# LineBot_2016.net
KiCad netlist of a schematic drawn in EAGLE
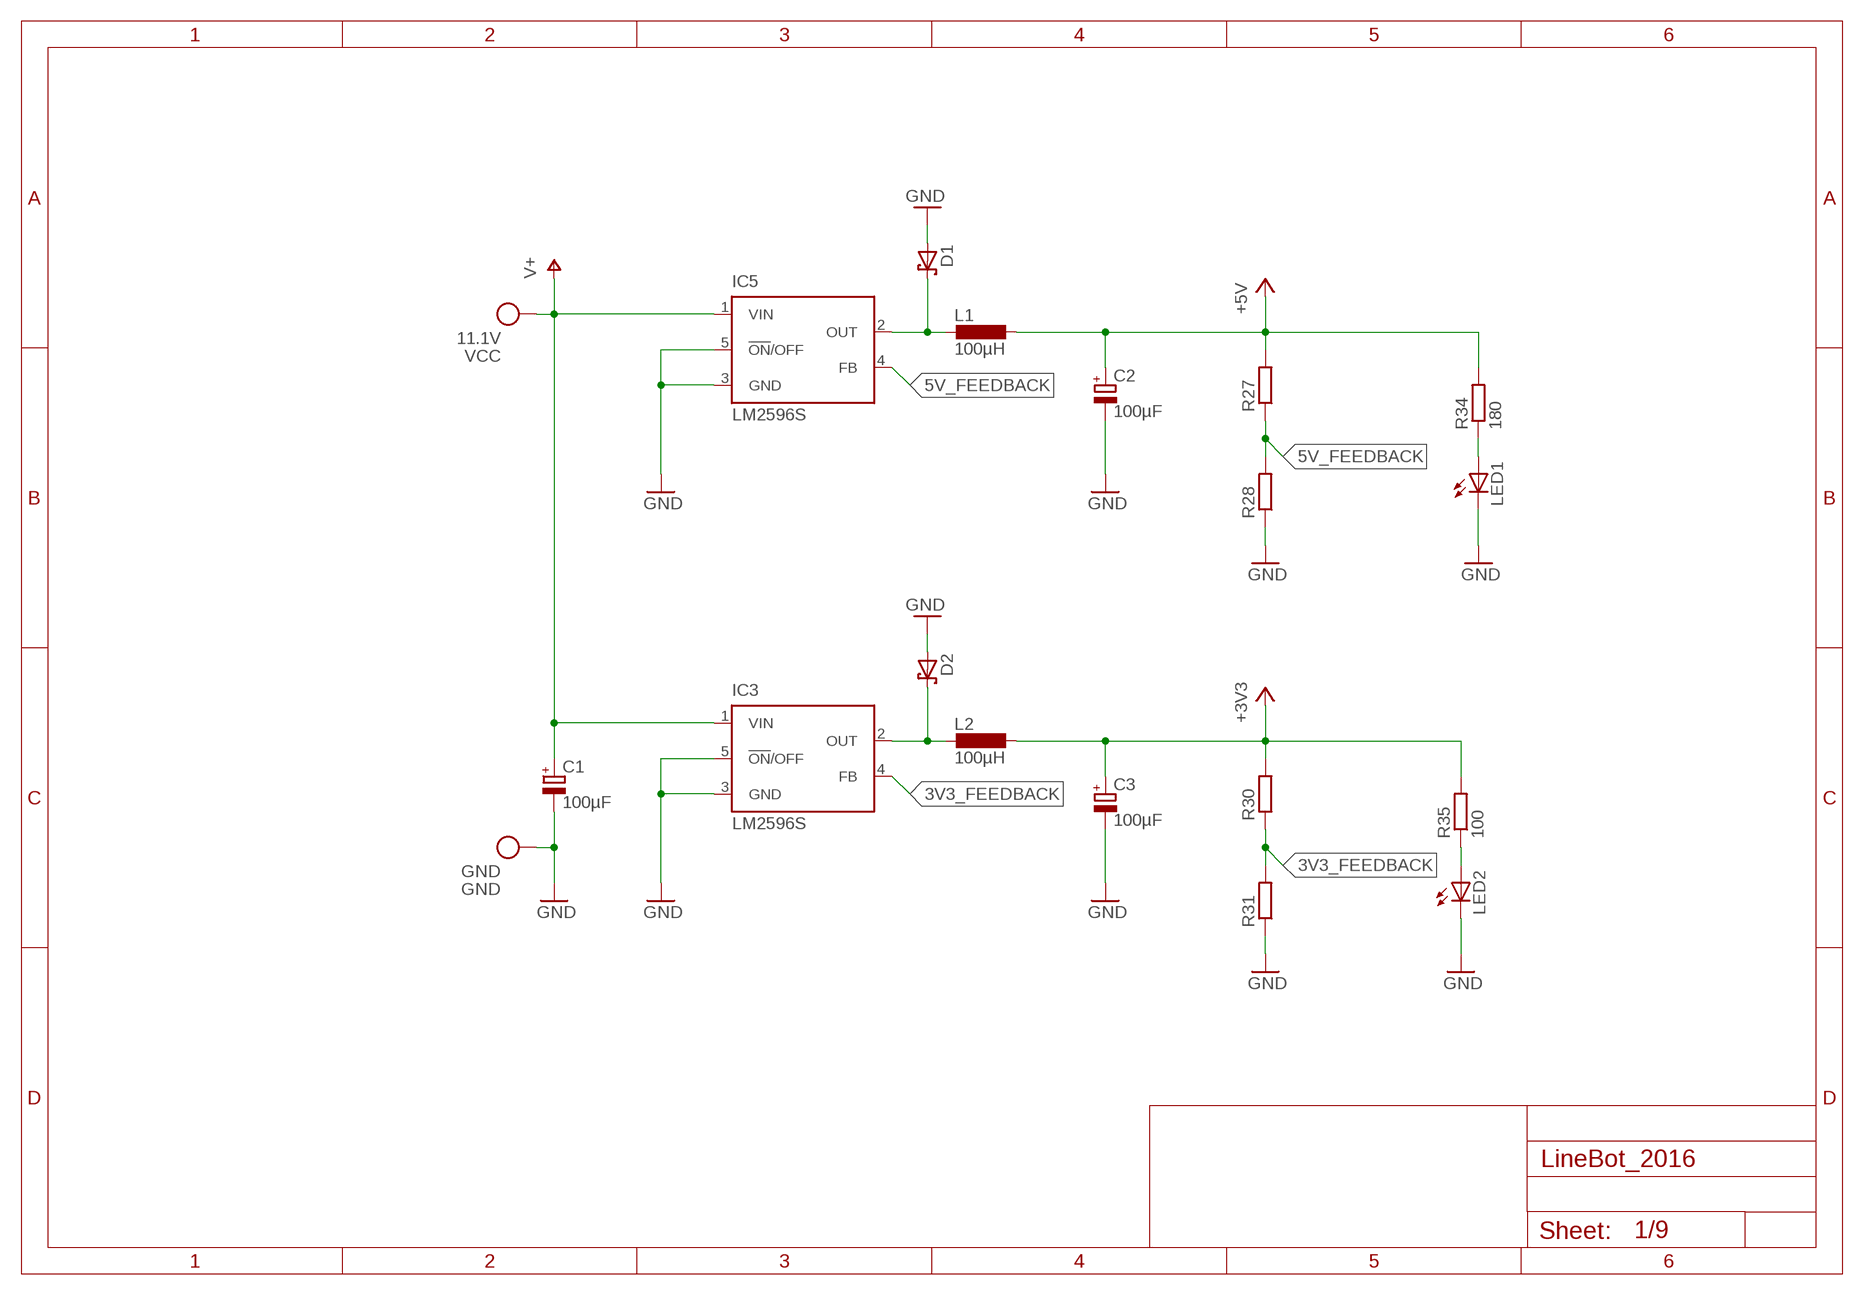
[diagram p0: schematic, sheet 1]
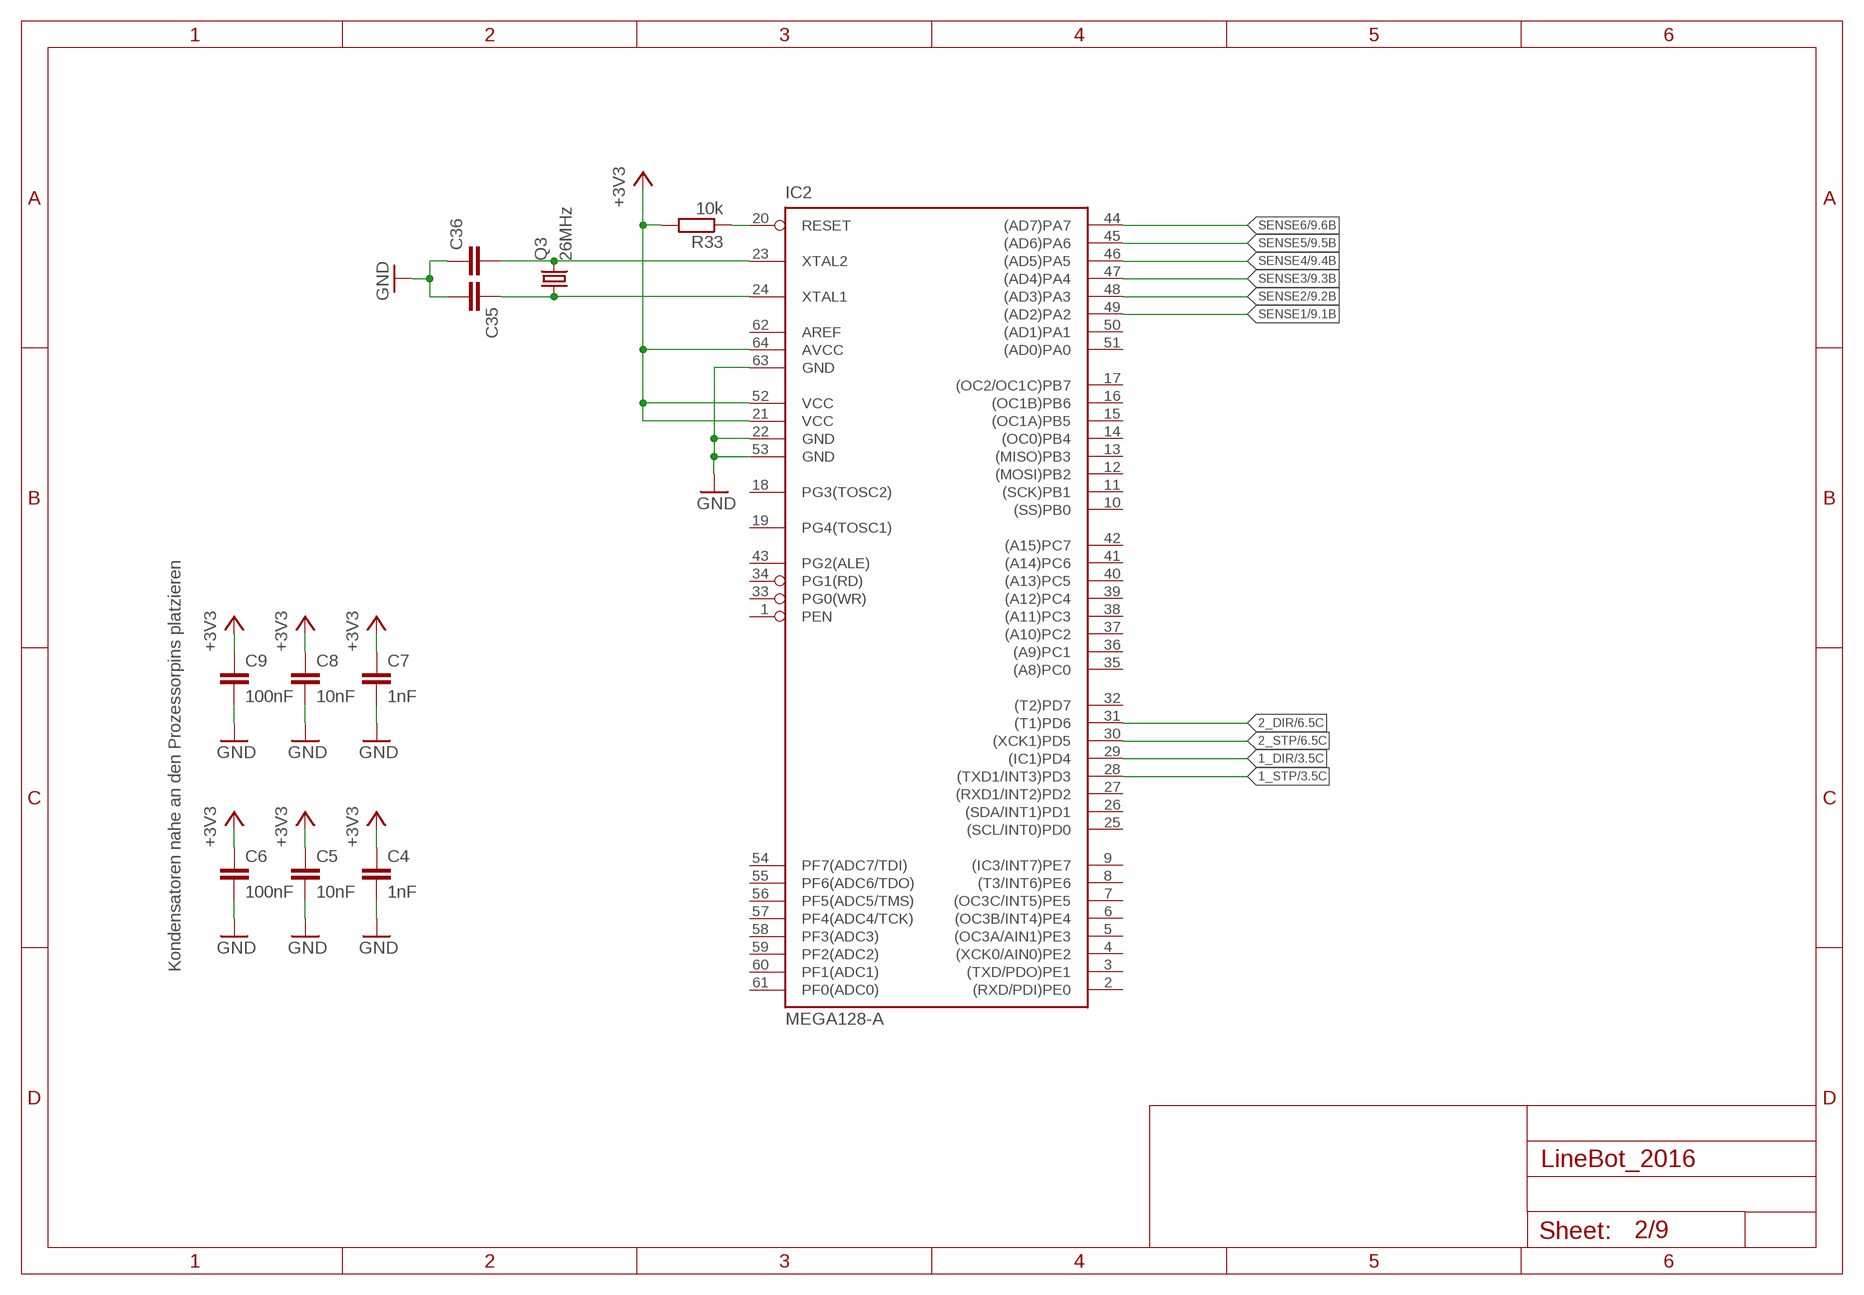
[diagram p1: schematic, sheet 2]
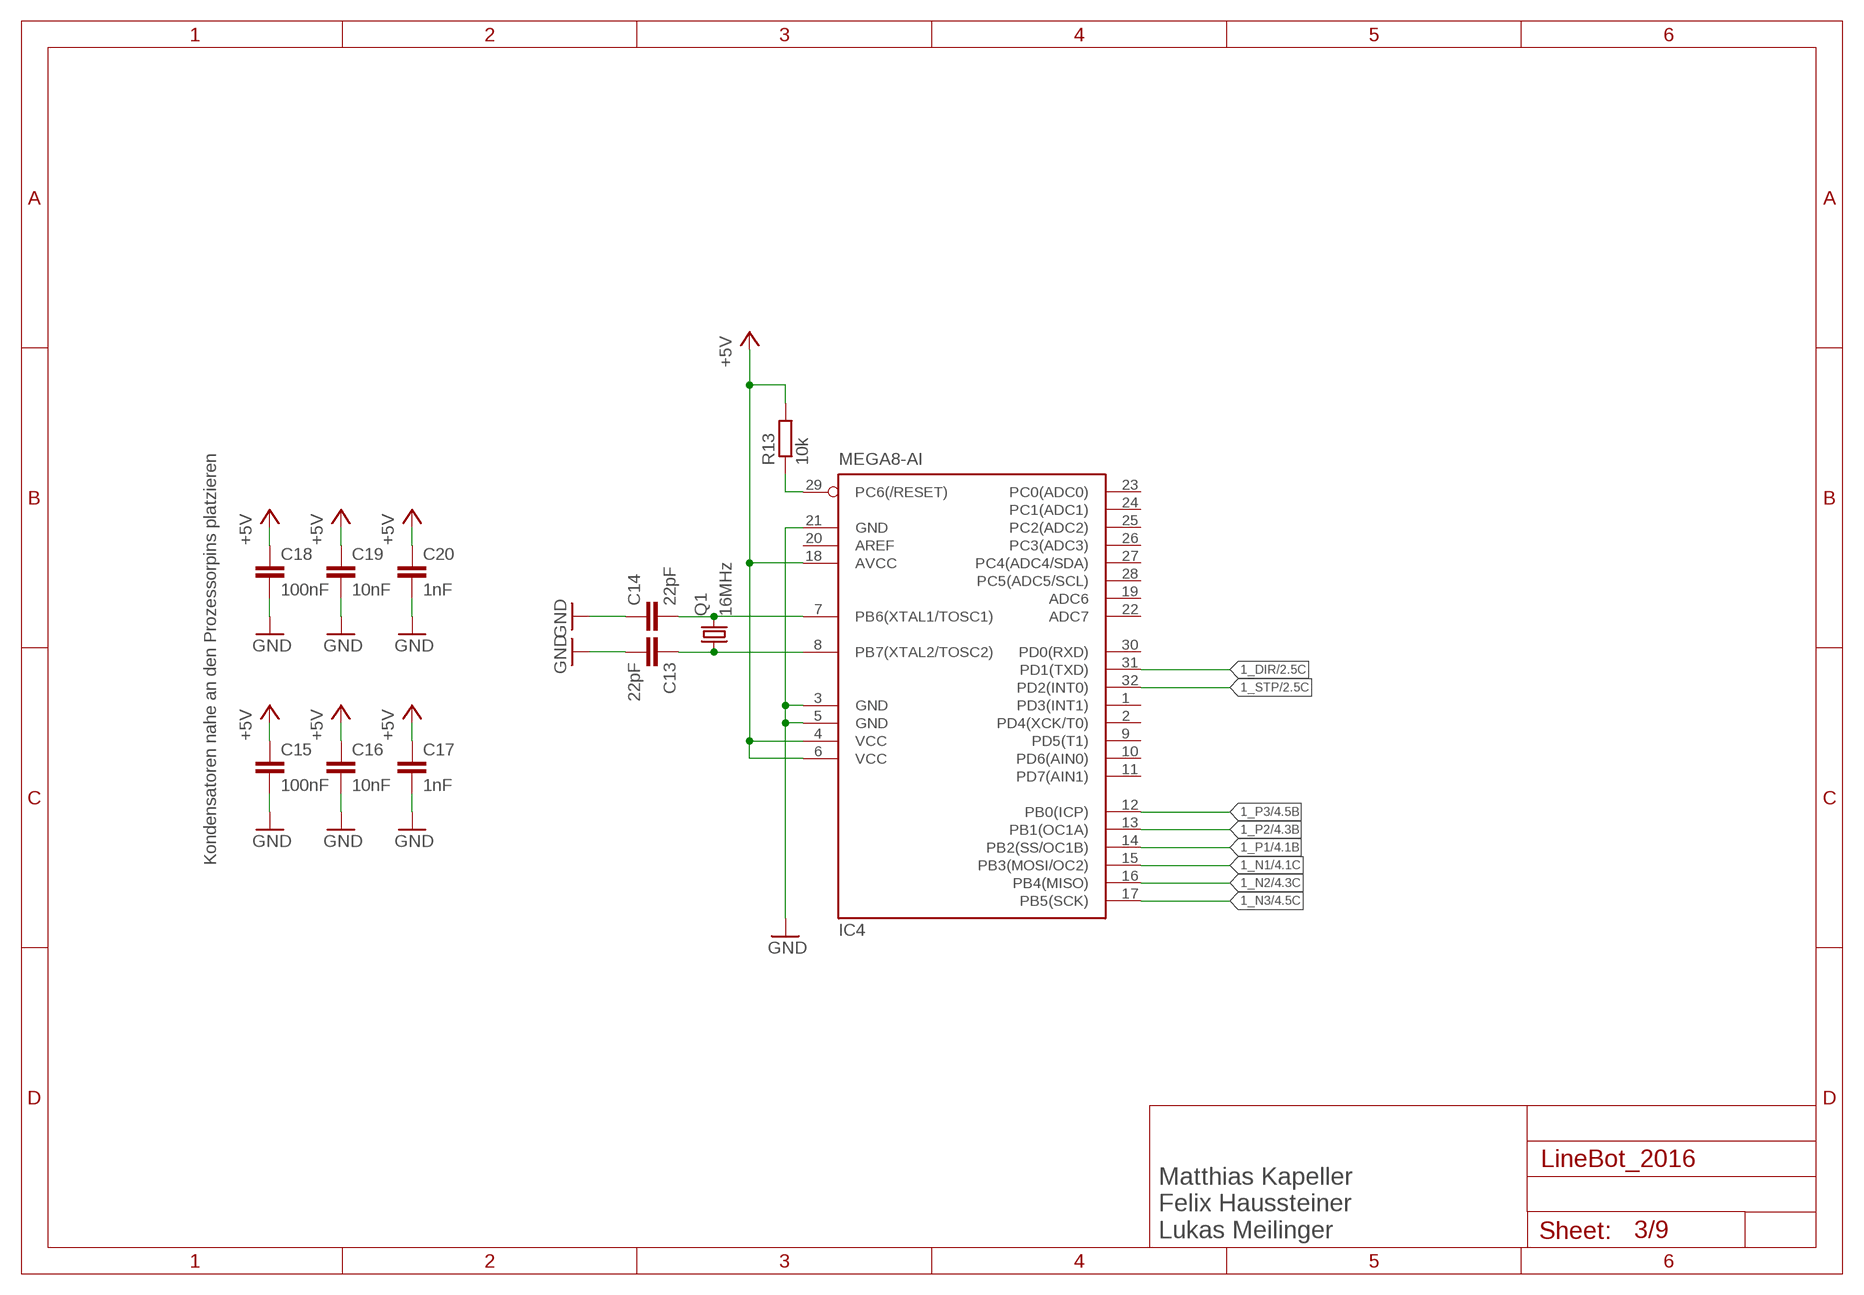
[diagram p2: schematic, sheet 3]
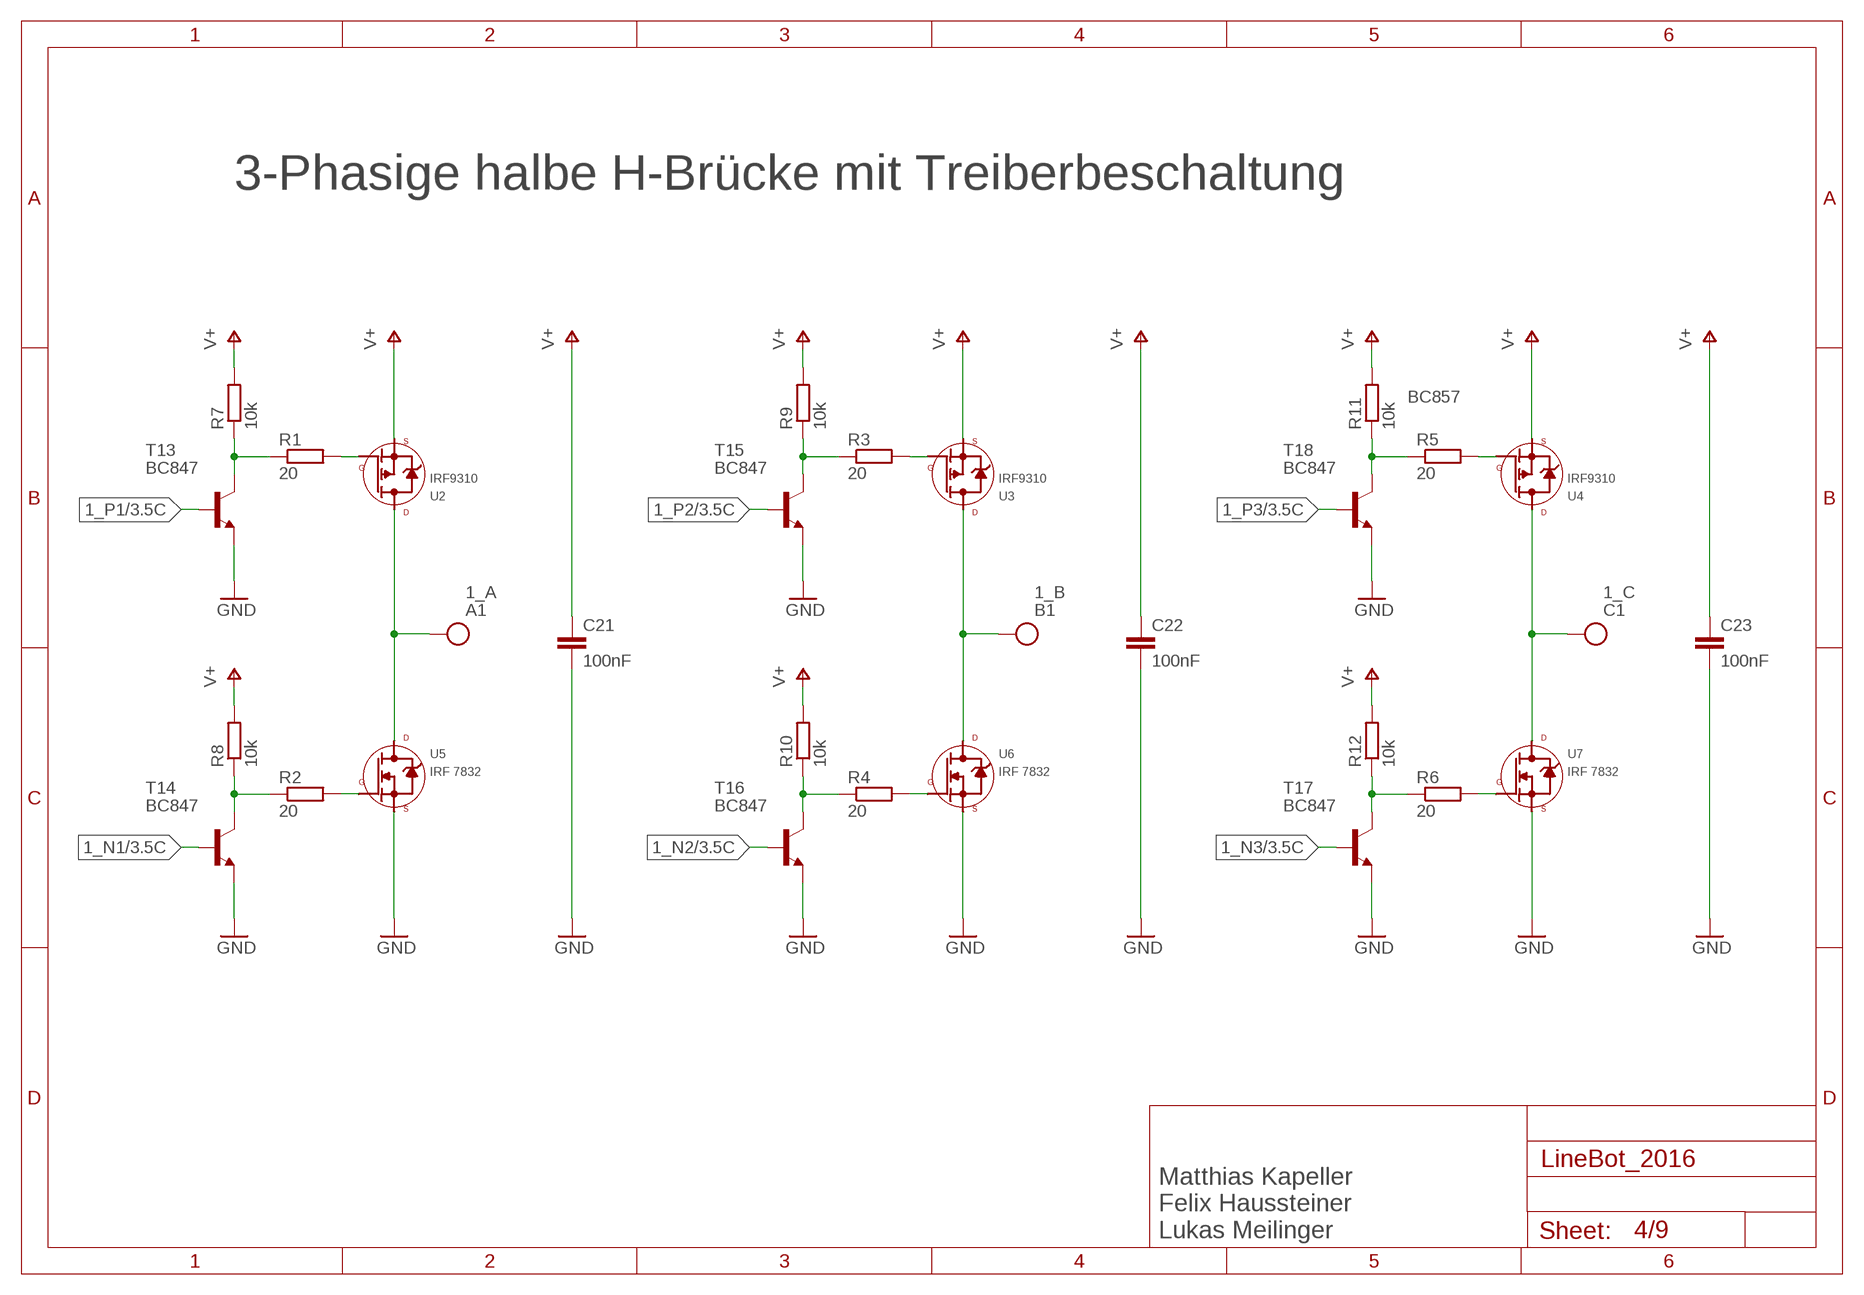
[diagram p3: schematic, sheet 4]
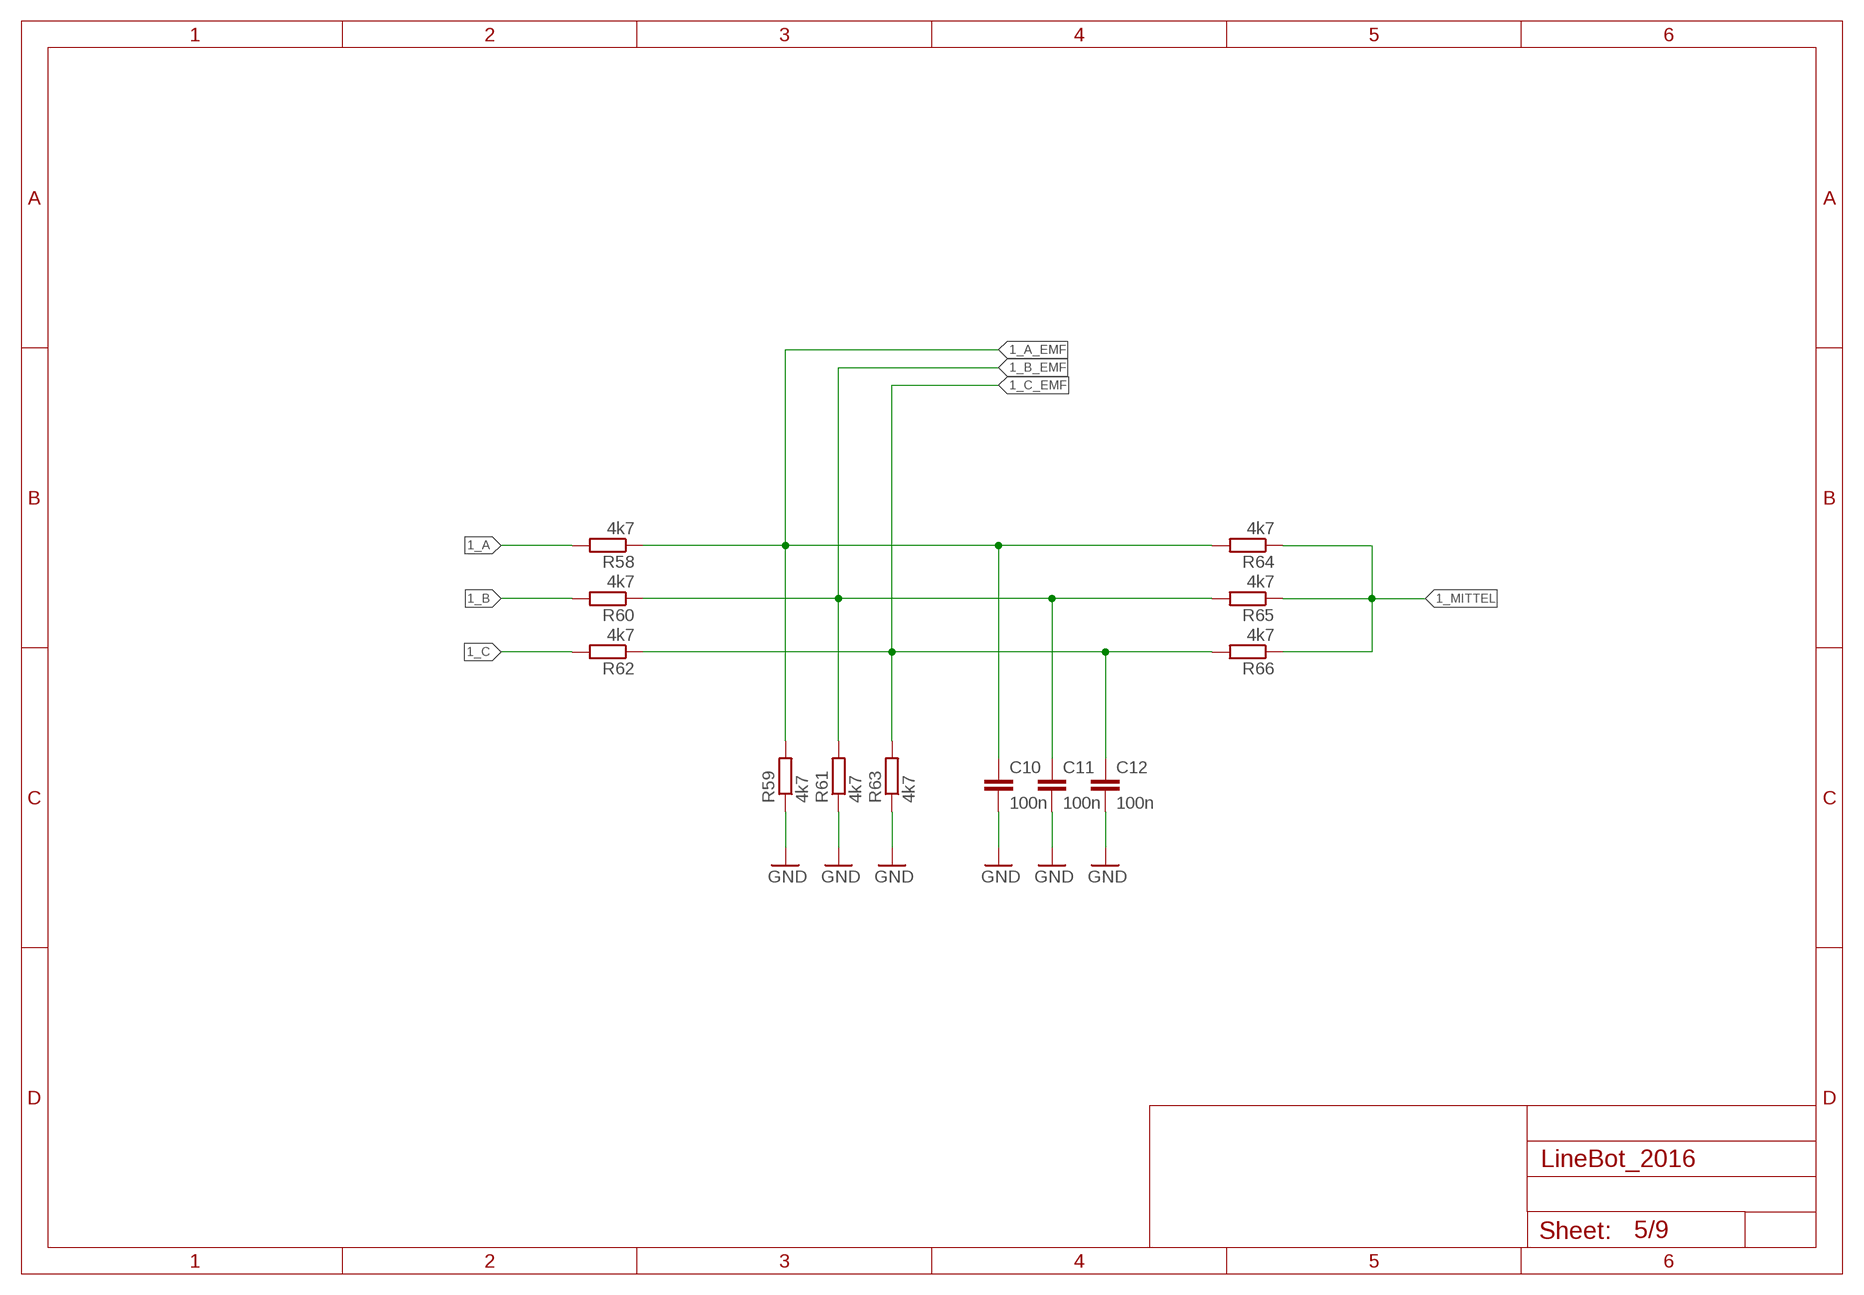
[diagram p4: schematic, sheet 5]
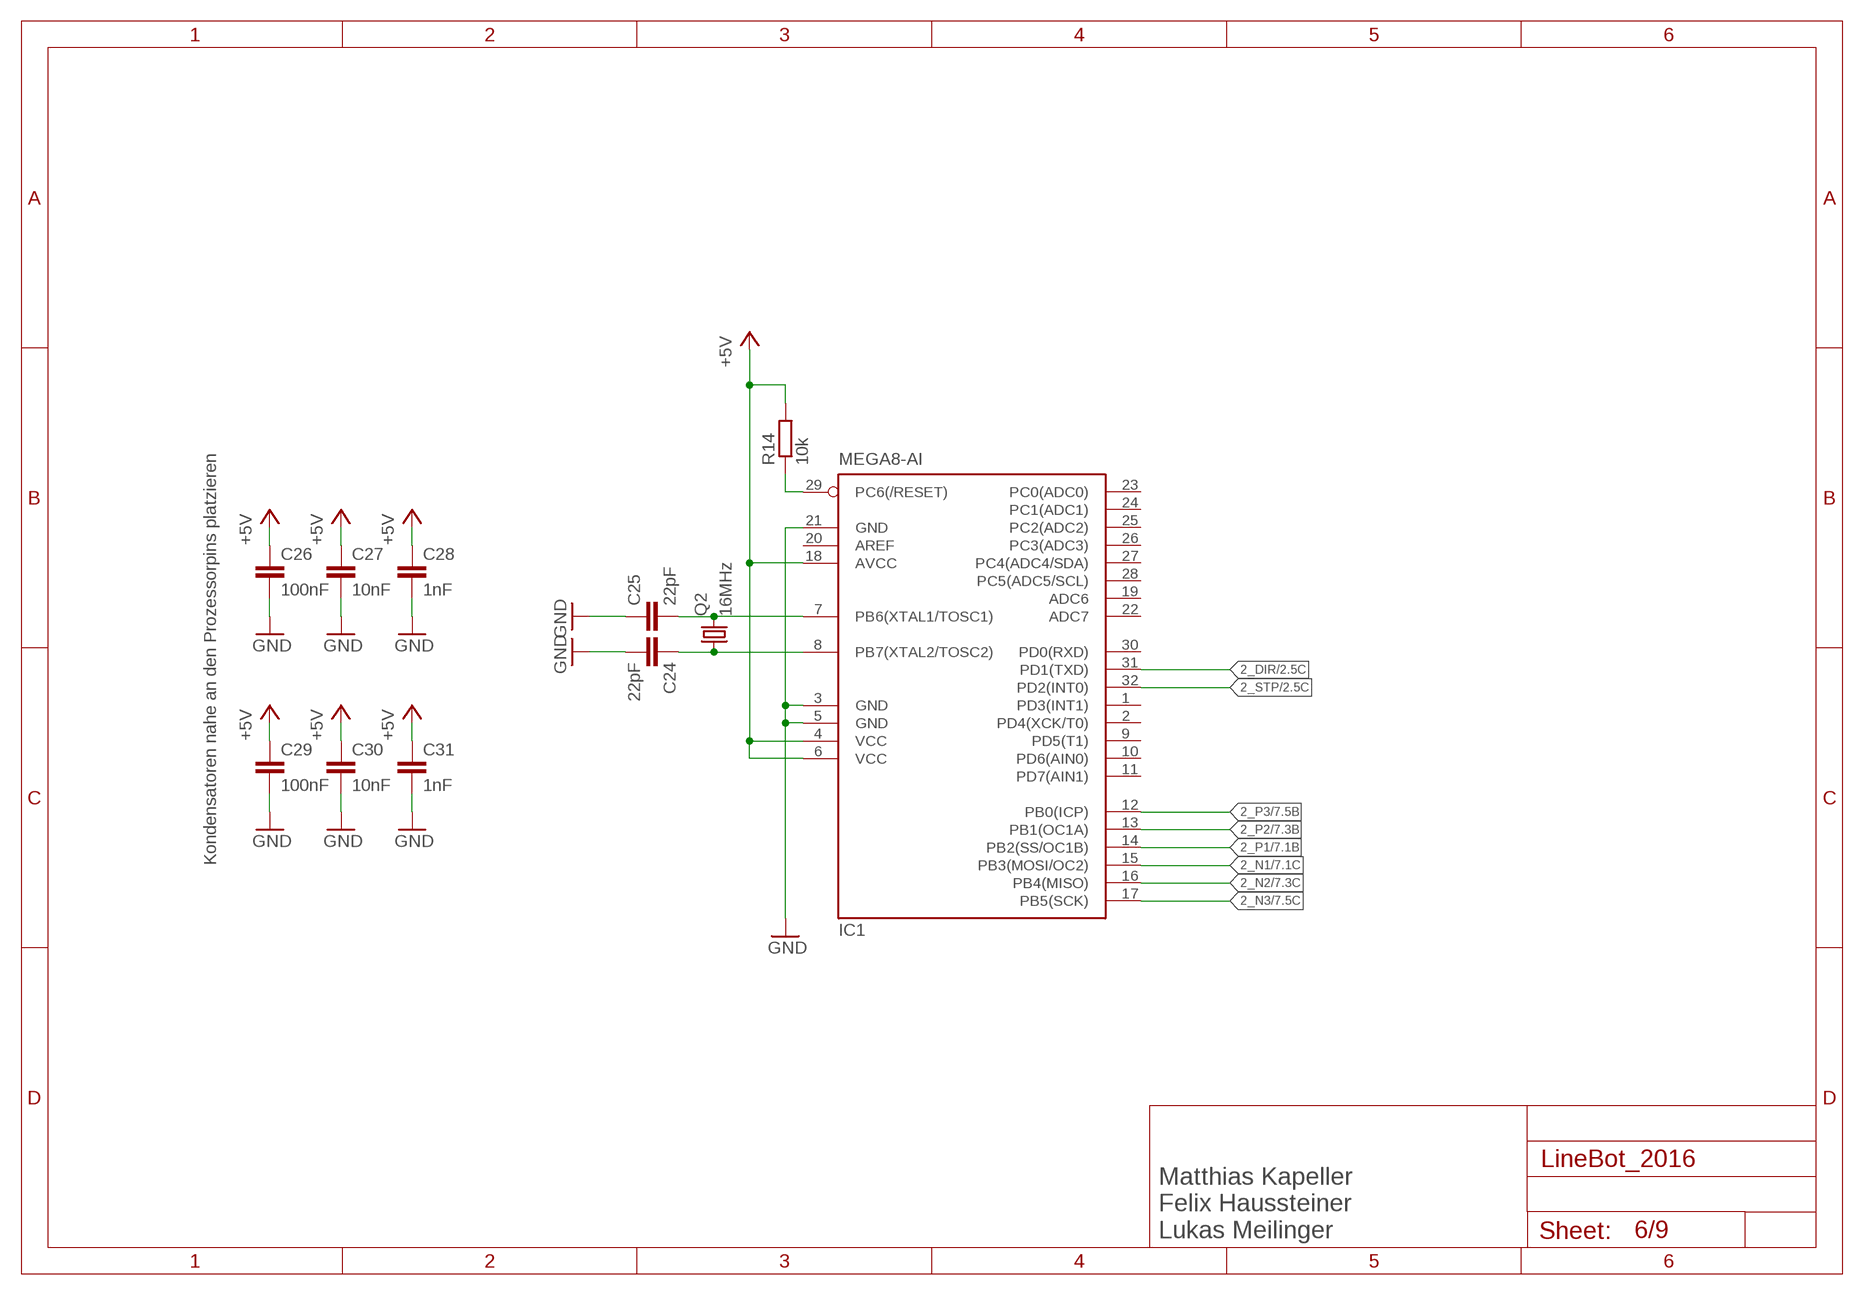
[diagram p5: schematic, sheet 6]
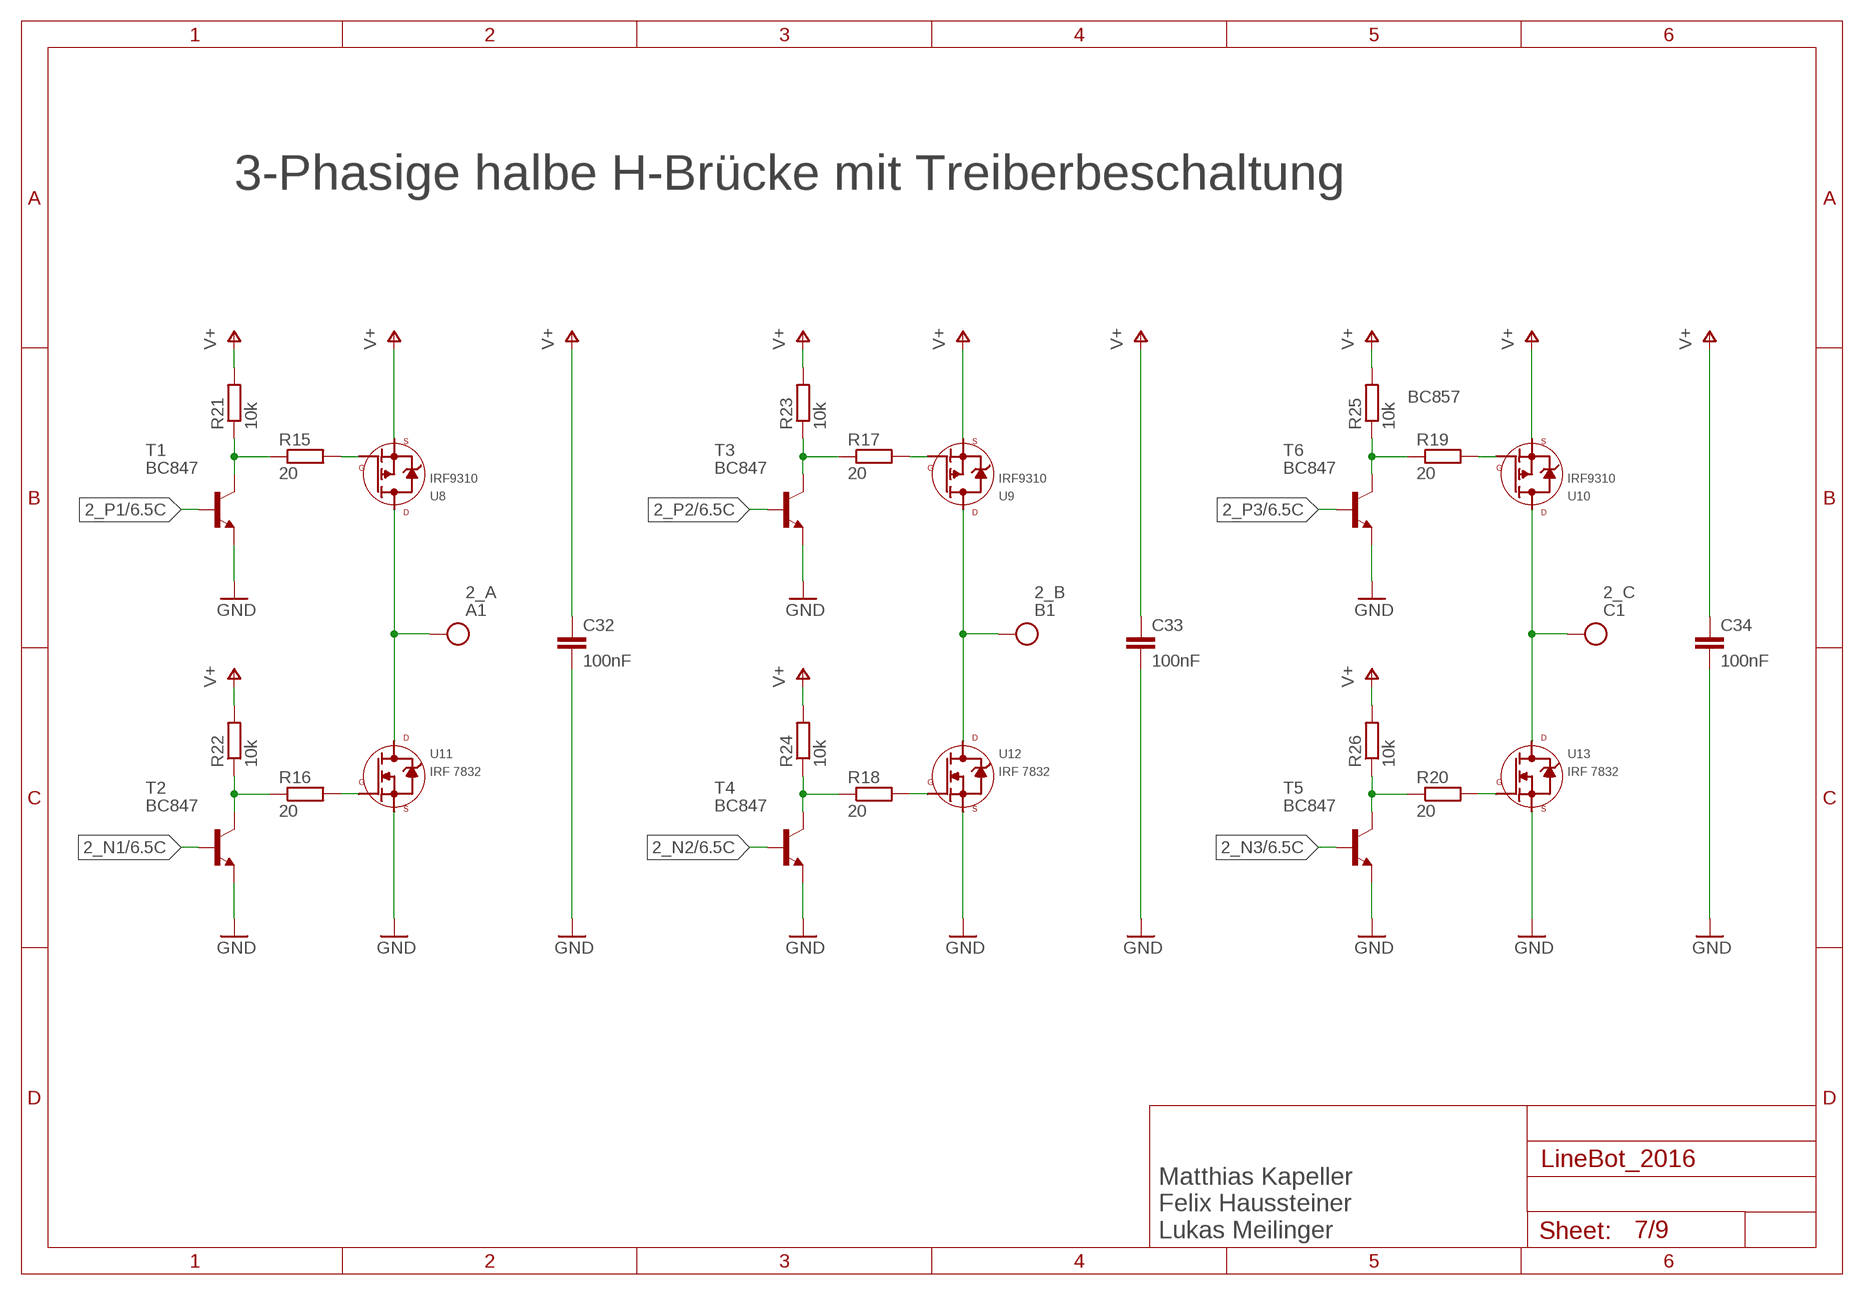
[diagram p6: schematic, sheet 7]
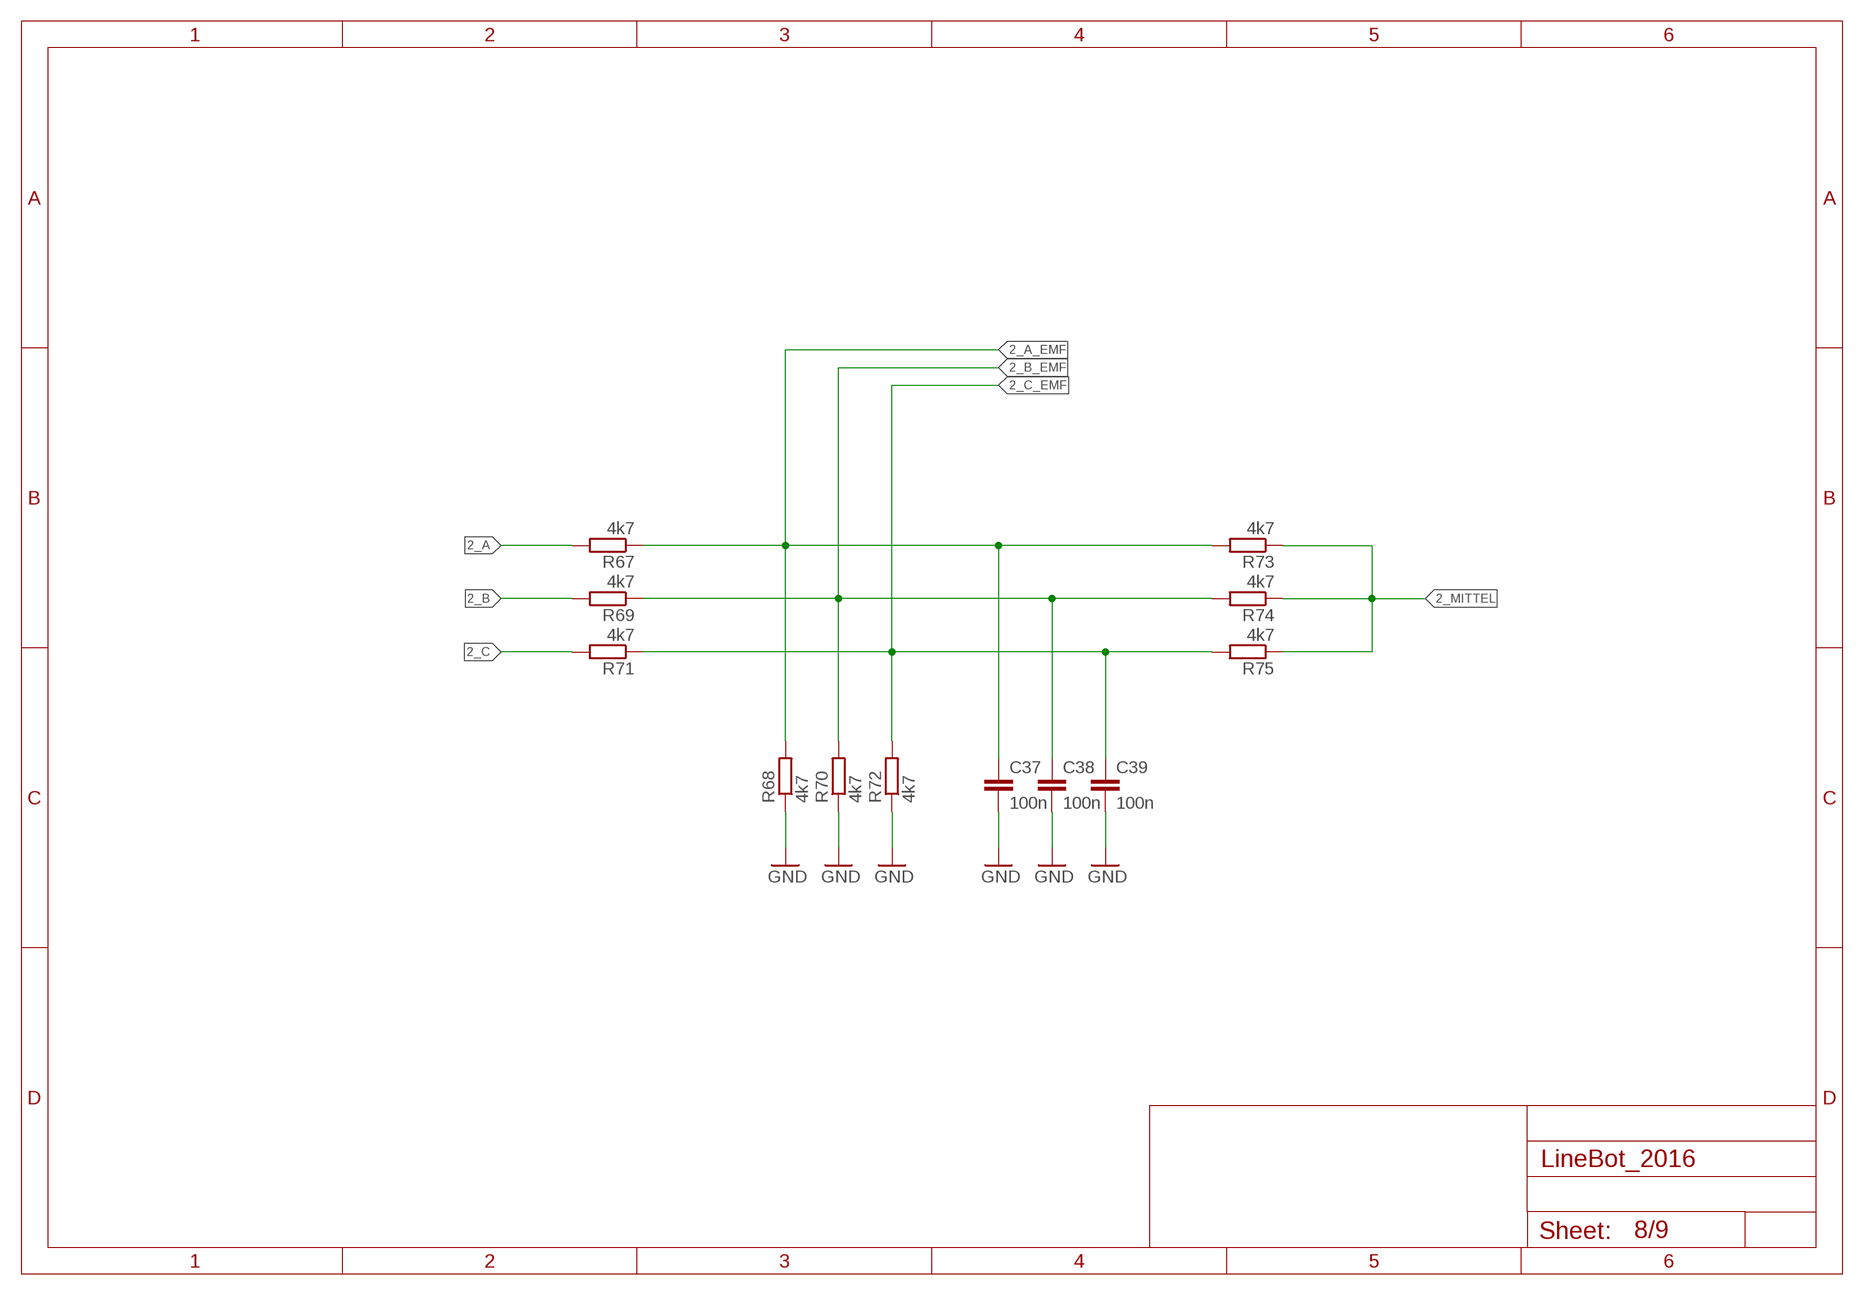
[diagram p7: schematic, sheet 8]
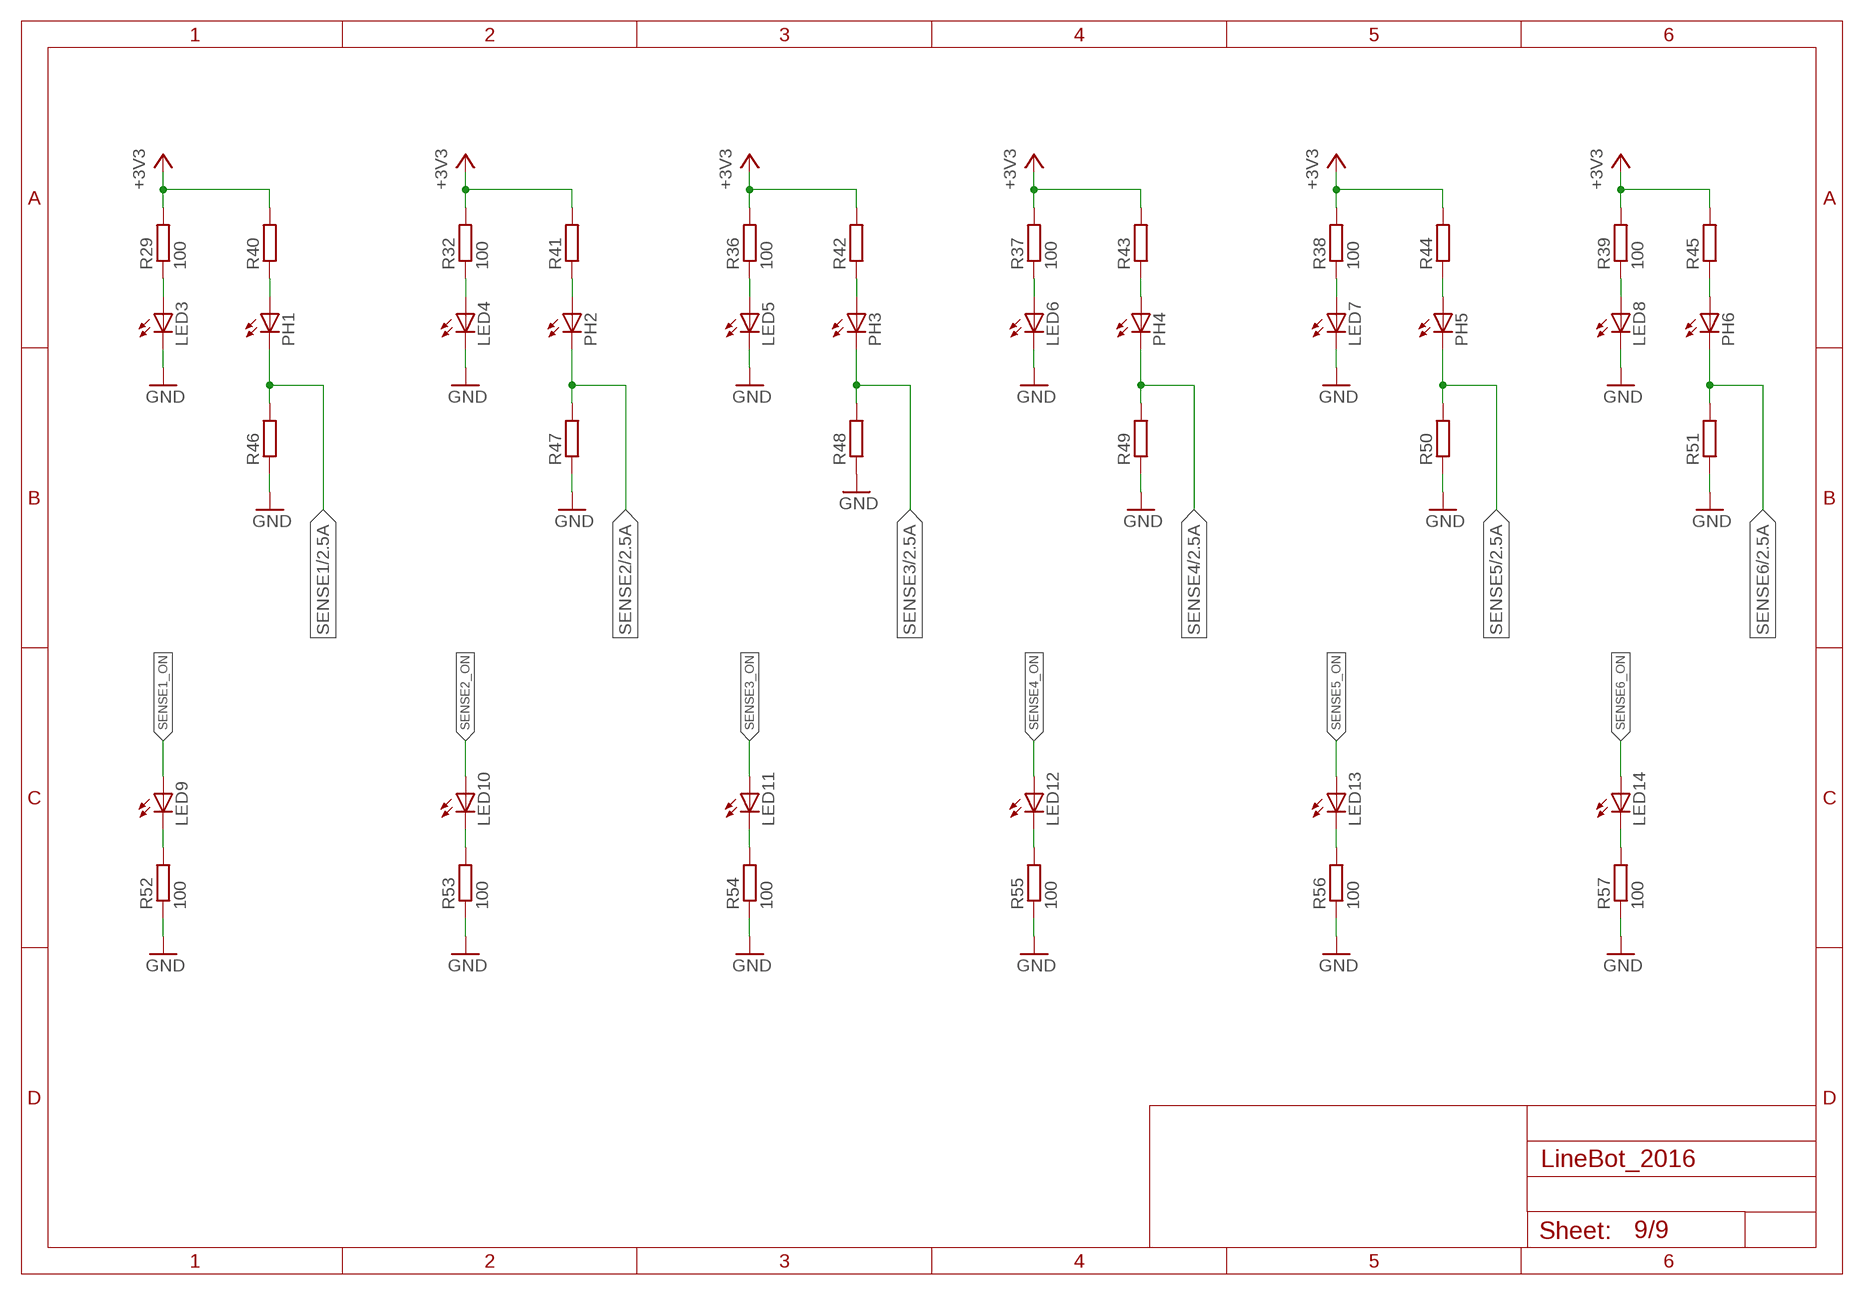
[diagram p8: schematic, sheet 9]

(export (version "E")
  (design (tool "Eeschema 10.0.6"))
  (components
    (comp (ref "1_A")
      (value "A1")
      (footprint "eagle-import:GOLDKONTAKT3MM")
      (libsource (lib "eagle-import") (part "GOLDKONTAKT_3MM"))
    )
    (comp (ref "1_B")
      (value "B1")
      (footprint "eagle-import:GOLDKONTAKT3MM")
      (libsource (lib "eagle-import") (part "GOLDKONTAKT_3MM"))
    )
    (comp (ref "1_C")
      (value "C1")
      (footprint "eagle-import:GOLDKONTAKT3MM")
      (libsource (lib "eagle-import") (part "GOLDKONTAKT_3MM"))
    )
    (comp (ref "C21")
      (value "100nF")
      (footprint "eagle-import:C1210")
      (libsource (lib "eagle-import") (part "C-EUC1210"))
    )
    (comp (ref "C22")
      (value "100nF")
      (footprint "eagle-import:C1210")
      (libsource (lib "eagle-import") (part "C-EUC1210"))
    )
    (comp (ref "C23")
      (value "100nF")
      (footprint "eagle-import:C1210")
      (libsource (lib "eagle-import") (part "C-EUC1210"))
    )
    (comp (ref "R1")
      (value "20")
      (footprint "eagle-import:R0805")
      (libsource (lib "eagle-import") (part "R-EU_R0805"))
    )
    (comp (ref "R2")
      (value "20")
      (footprint "eagle-import:R0805")
      (libsource (lib "eagle-import") (part "R-EU_R0805"))
    )
    (comp (ref "R3")
      (value "20")
      (footprint "eagle-import:R0805")
      (libsource (lib "eagle-import") (part "R-EU_R0805"))
    )
    (comp (ref "R4")
      (value "20")
      (footprint "eagle-import:R0805")
      (libsource (lib "eagle-import") (part "R-EU_R0805"))
    )
    (comp (ref "R5")
      (value "20")
      (footprint "eagle-import:R0805")
      (libsource (lib "eagle-import") (part "R-EU_R0805"))
    )
    (comp (ref "R6")
      (value "20")
      (footprint "eagle-import:R0805")
      (libsource (lib "eagle-import") (part "R-EU_R0805"))
    )
    (comp (ref "R7")
      (value "10k")
      (footprint "eagle-import:R0805")
      (libsource (lib "eagle-import") (part "R-EU_R0805"))
    )
    (comp (ref "R8")
      (value "10k")
      (footprint "eagle-import:R0805")
      (libsource (lib "eagle-import") (part "R-EU_R0805"))
    )
    (comp (ref "R9")
      (value "10k")
      (footprint "eagle-import:R0805")
      (libsource (lib "eagle-import") (part "R-EU_R0805"))
    )
    (comp (ref "R10")
      (value "10k")
      (footprint "eagle-import:R0805")
      (libsource (lib "eagle-import") (part "R-EU_R0805"))
    )
    (comp (ref "R11")
      (value "10k")
      (footprint "eagle-import:R0805")
      (libsource (lib "eagle-import") (part "R-EU_R0805"))
    )
    (comp (ref "R12")
      (value "10k")
      (footprint "eagle-import:R0805")
      (libsource (lib "eagle-import") (part "R-EU_R0805"))
    )
    (comp (ref "T13")
      (value "BC847")
      (footprint "eagle-import:SOT23")
      (libsource (lib "eagle-import") (part "BC847"))
    )
    (comp (ref "T14")
      (value "BC847")
      (footprint "eagle-import:SOT23")
      (libsource (lib "eagle-import") (part "BC847"))
    )
    (comp (ref "T15")
      (value "BC847")
      (footprint "eagle-import:SOT23")
      (libsource (lib "eagle-import") (part "BC847"))
    )
    (comp (ref "T16")
      (value "BC847")
      (footprint "eagle-import:SOT23")
      (libsource (lib "eagle-import") (part "BC847"))
    )
    (comp (ref "T17")
      (value "BC847")
      (footprint "eagle-import:SOT23")
      (libsource (lib "eagle-import") (part "BC847"))
    )
    (comp (ref "T18")
      (value "BC847")
      (footprint "eagle-import:SOT23")
      (libsource (lib "eagle-import") (part "BC847"))
    )
    (comp (ref "U2")
      (value "IRF9310")
      (footprint "eagle-import:SO8")
      (libsource (lib "eagle-import") (part "IRF9310"))
    )
    (comp (ref "U3")
      (value "IRF9310")
      (footprint "eagle-import:SO8")
      (libsource (lib "eagle-import") (part "IRF9310"))
    )
    (comp (ref "U4")
      (value "IRF9310")
      (footprint "eagle-import:SO8")
      (libsource (lib "eagle-import") (part "IRF9310"))
    )
    (comp (ref "U5")
      (value "IRF7832")
      (footprint "eagle-import:SO8")
      (libsource (lib "eagle-import") (part "IRF7832"))
    )
    (comp (ref "U6")
      (value "IRF7832")
      (footprint "eagle-import:SO8")
      (libsource (lib "eagle-import") (part "IRF7832"))
    )
    (comp (ref "U7")
      (value "IRF7832")
      (footprint "eagle-import:SO8")
      (libsource (lib "eagle-import") (part "IRF7832"))
    )
    (comp (ref "C10")
      (value "100n")
      (footprint "eagle-import:C0805")
      (libsource (lib "eagle-import") (part "C-EUC0805"))
    )
    (comp (ref "C11")
      (value "100n")
      (footprint "eagle-import:C0805")
      (libsource (lib "eagle-import") (part "C-EUC0805"))
    )
    (comp (ref "C12")
      (value "100n")
      (footprint "eagle-import:C0805")
      (libsource (lib "eagle-import") (part "C-EUC0805"))
    )
    (comp (ref "R58")
      (value "4k7")
      (footprint "eagle-import:R0805")
      (libsource (lib "eagle-import") (part "R-EU_R0805"))
    )
    (comp (ref "R59")
      (value "4k7")
      (footprint "eagle-import:R0805")
      (libsource (lib "eagle-import") (part "R-EU_R0805"))
    )
    (comp (ref "R60")
      (value "4k7")
      (footprint "eagle-import:R0805")
      (libsource (lib "eagle-import") (part "R-EU_R0805"))
    )
    (comp (ref "R61")
      (value "4k7")
      (footprint "eagle-import:R0805")
      (libsource (lib "eagle-import") (part "R-EU_R0805"))
    )
    (comp (ref "R62")
      (value "4k7")
      (footprint "eagle-import:R0805")
      (libsource (lib "eagle-import") (part "R-EU_R0805"))
    )
    (comp (ref "R63")
      (value "4k7")
      (footprint "eagle-import:R0805")
      (libsource (lib "eagle-import") (part "R-EU_R0805"))
    )
    (comp (ref "R64")
      (value "4k7")
      (footprint "eagle-import:R0805")
      (libsource (lib "eagle-import") (part "R-EU_R0805"))
    )
    (comp (ref "R65")
      (value "4k7")
      (footprint "eagle-import:R0805")
      (libsource (lib "eagle-import") (part "R-EU_R0805"))
    )
    (comp (ref "R66")
      (value "4k7")
      (footprint "eagle-import:R0805")
      (libsource (lib "eagle-import") (part "R-EU_R0805"))
    )
    (comp (ref "2_A")
      (value "A1")
      (footprint "eagle-import:GOLDKONTAKT3MM")
      (libsource (lib "eagle-import") (part "GOLDKONTAKT_3MM"))
    )
    (comp (ref "2_B")
      (value "B1")
      (footprint "eagle-import:GOLDKONTAKT3MM")
      (libsource (lib "eagle-import") (part "GOLDKONTAKT_3MM"))
    )
    (comp (ref "2_C")
      (value "C1")
      (footprint "eagle-import:GOLDKONTAKT3MM")
      (libsource (lib "eagle-import") (part "GOLDKONTAKT_3MM"))
    )
    (comp (ref "C32")
      (value "100nF")
      (footprint "eagle-import:C1210")
      (libsource (lib "eagle-import") (part "C-EUC1210"))
    )
    (comp (ref "C33")
      (value "100nF")
      (footprint "eagle-import:C1210")
      (libsource (lib "eagle-import") (part "C-EUC1210"))
    )
    (comp (ref "C34")
      (value "100nF")
      (footprint "eagle-import:C1210")
      (libsource (lib "eagle-import") (part "C-EUC1210"))
    )
    (comp (ref "R15")
      (value "20")
      (footprint "eagle-import:R0805")
      (libsource (lib "eagle-import") (part "R-EU_R0805"))
    )
    (comp (ref "R16")
      (value "20")
      (footprint "eagle-import:R0805")
      (libsource (lib "eagle-import") (part "R-EU_R0805"))
    )
    (comp (ref "R17")
      (value "20")
      (footprint "eagle-import:R0805")
      (libsource (lib "eagle-import") (part "R-EU_R0805"))
    )
    (comp (ref "R18")
      (value "20")
      (footprint "eagle-import:R0805")
      (libsource (lib "eagle-import") (part "R-EU_R0805"))
    )
    (comp (ref "R19")
      (value "20")
      (footprint "eagle-import:R0805")
      (libsource (lib "eagle-import") (part "R-EU_R0805"))
    )
    (comp (ref "R20")
      (value "20")
      (footprint "eagle-import:R0805")
      (libsource (lib "eagle-import") (part "R-EU_R0805"))
    )
    (comp (ref "R21")
      (value "10k")
      (footprint "eagle-import:R0805")
      (libsource (lib "eagle-import") (part "R-EU_R0805"))
    )
    (comp (ref "R22")
      (value "10k")
      (footprint "eagle-import:R0805")
      (libsource (lib "eagle-import") (part "R-EU_R0805"))
    )
    (comp (ref "R23")
      (value "10k")
      (footprint "eagle-import:R0805")
      (libsource (lib "eagle-import") (part "R-EU_R0805"))
    )
    (comp (ref "R24")
      (value "10k")
      (footprint "eagle-import:R0805")
      (libsource (lib "eagle-import") (part "R-EU_R0805"))
    )
    (comp (ref "R25")
      (value "10k")
      (footprint "eagle-import:R0805")
      (libsource (lib "eagle-import") (part "R-EU_R0805"))
    )
    (comp (ref "R26")
      (value "10k")
      (footprint "eagle-import:R0805")
      (libsource (lib "eagle-import") (part "R-EU_R0805"))
    )
    (comp (ref "T1")
      (value "BC847")
      (footprint "eagle-import:SOT23")
      (libsource (lib "eagle-import") (part "BC847"))
    )
    (comp (ref "T2")
      (value "BC847")
      (footprint "eagle-import:SOT23")
      (libsource (lib "eagle-import") (part "BC847"))
    )
    (comp (ref "T3")
      (value "BC847")
      (footprint "eagle-import:SOT23")
      (libsource (lib "eagle-import") (part "BC847"))
    )
    (comp (ref "T4")
      (value "BC847")
      (footprint "eagle-import:SOT23")
      (libsource (lib "eagle-import") (part "BC847"))
    )
    (comp (ref "T5")
      (value "BC847")
      (footprint "eagle-import:SOT23")
      (libsource (lib "eagle-import") (part "BC847"))
    )
    (comp (ref "T6")
      (value "BC847")
      (footprint "eagle-import:SOT23")
      (libsource (lib "eagle-import") (part "BC847"))
    )
    (comp (ref "U8")
      (value "IRF9310")
      (footprint "eagle-import:SO8")
      (libsource (lib "eagle-import") (part "IRF9310"))
    )
    (comp (ref "U9")
      (value "IRF9310")
      (footprint "eagle-import:SO8")
      (libsource (lib "eagle-import") (part "IRF9310"))
    )
    (comp (ref "U10")
      (value "IRF9310")
      (footprint "eagle-import:SO8")
      (libsource (lib "eagle-import") (part "IRF9310"))
    )
    (comp (ref "U11")
      (value "IRF7832")
      (footprint "eagle-import:SO8")
      (libsource (lib "eagle-import") (part "IRF7832"))
    )
    (comp (ref "U12")
      (value "IRF7832")
      (footprint "eagle-import:SO8")
      (libsource (lib "eagle-import") (part "IRF7832"))
    )
    (comp (ref "U13")
      (value "IRF7832")
      (footprint "eagle-import:SO8")
      (libsource (lib "eagle-import") (part "IRF7832"))
    )
    (comp (ref "C13")
      (value "22pF")
      (footprint "eagle-import:C0805")
      (libsource (lib "eagle-import") (part "C-EUC0805"))
    )
    (comp (ref "C14")
      (value "22pF")
      (footprint "eagle-import:C0805")
      (libsource (lib "eagle-import") (part "C-EUC0805"))
    )
    (comp (ref "C15")
      (value "100nF")
      (footprint "eagle-import:C0805")
      (libsource (lib "eagle-import") (part "C-EUC0805"))
    )
    (comp (ref "C16")
      (value "10nF")
      (footprint "eagle-import:C0805")
      (libsource (lib "eagle-import") (part "C-EUC0805"))
    )
    (comp (ref "C17")
      (value "1nF")
      (footprint "eagle-import:C0805")
      (libsource (lib "eagle-import") (part "C-EUC0805"))
    )
    (comp (ref "C18")
      (value "100nF")
      (footprint "eagle-import:C0805")
      (libsource (lib "eagle-import") (part "C-EUC0805"))
    )
    (comp (ref "C19")
      (value "10nF")
      (footprint "eagle-import:C0805")
      (libsource (lib "eagle-import") (part "C-EUC0805"))
    )
    (comp (ref "C20")
      (value "1nF")
      (footprint "eagle-import:C0805")
      (libsource (lib "eagle-import") (part "C-EUC0805"))
    )
    (comp (ref "IC4")
      (value "MEGA8-AI")
      (footprint "eagle-import:TQFP32-08")
      (fields (field (name "MPN") "ATMEGA8-16AU"))
      (libsource (lib "eagle-import") (part "MEGA8-AI"))
    )
    (comp (ref "Q1")
      (value "16MHz")
      (footprint "eagle-import:HC49U-V")
      (libsource (lib "eagle-import") (part "CRYSTALHC49U-V"))
    )
    (comp (ref "R13")
      (value "10k")
      (footprint "eagle-import:R0805")
      (libsource (lib "eagle-import") (part "R-EU_R0805"))
    )
    (comp (ref "C24")
      (value "22pF")
      (footprint "eagle-import:C0805")
      (libsource (lib "eagle-import") (part "C-EUC0805"))
    )
    (comp (ref "C25")
      (value "22pF")
      (footprint "eagle-import:C0805")
      (libsource (lib "eagle-import") (part "C-EUC0805"))
    )
    (comp (ref "C26")
      (value "100nF")
      (footprint "eagle-import:C0805")
      (libsource (lib "eagle-import") (part "C-EUC0805"))
    )
    (comp (ref "C27")
      (value "10nF")
      (footprint "eagle-import:C0805")
      (libsource (lib "eagle-import") (part "C-EUC0805"))
    )
    (comp (ref "C28")
      (value "1nF")
      (footprint "eagle-import:C0805")
      (libsource (lib "eagle-import") (part "C-EUC0805"))
    )
    (comp (ref "C29")
      (value "100nF")
      (footprint "eagle-import:C0805")
      (libsource (lib "eagle-import") (part "C-EUC0805"))
    )
    (comp (ref "C30")
      (value "10nF")
      (footprint "eagle-import:C0805")
      (libsource (lib "eagle-import") (part "C-EUC0805"))
    )
    (comp (ref "C31")
      (value "1nF")
      (footprint "eagle-import:C0805")
      (libsource (lib "eagle-import") (part "C-EUC0805"))
    )
    (comp (ref "IC1")
      (value "MEGA8-AI")
      (footprint "eagle-import:TQFP32-08")
      (fields (field (name "MPN") "ATMEGA8-16AU"))
      (libsource (lib "eagle-import") (part "MEGA8-AI"))
    )
    (comp (ref "Q2")
      (value "16MHz")
      (footprint "eagle-import:HC49U-V")
      (libsource (lib "eagle-import") (part "CRYSTALHC49U-V"))
    )
    (comp (ref "R14")
      (value "10k")
      (footprint "eagle-import:R0805")
      (libsource (lib "eagle-import") (part "R-EU_R0805"))
    )
    (comp (ref "C4")
      (value "1nF")
      (footprint "eagle-import:C0805")
      (libsource (lib "eagle-import") (part "C-EUC0805"))
    )
    (comp (ref "C5")
      (value "10nF")
      (footprint "eagle-import:C0805")
      (libsource (lib "eagle-import") (part "C-EUC0805"))
    )
    (comp (ref "C6")
      (value "100nF")
      (footprint "eagle-import:C0805")
      (libsource (lib "eagle-import") (part "C-EUC0805"))
    )
    (comp (ref "C7")
      (value "1nF")
      (footprint "eagle-import:C0805")
      (libsource (lib "eagle-import") (part "C-EUC0805"))
    )
    (comp (ref "C8")
      (value "10nF")
      (footprint "eagle-import:C0805")
      (libsource (lib "eagle-import") (part "C-EUC0805"))
    )
    (comp (ref "C9")
      (value "100nF")
      (footprint "eagle-import:C0805")
      (libsource (lib "eagle-import") (part "C-EUC0805"))
    )
    (comp (ref "C35")
      (value "C-EUC0805")
      (footprint "eagle-import:C0805")
      (libsource (lib "eagle-import") (part "C-EUC0805"))
    )
    (comp (ref "C36")
      (value "C-EUC0805")
      (footprint "eagle-import:C0805")
      (libsource (lib "eagle-import") (part "C-EUC0805"))
    )
    (comp (ref "IC2")
      (value "MEGA128-A")
      (footprint "eagle-import:TQFP64")
      (fields (field (name "MPN") "ATMEGA128-16AU"))
      (libsource (lib "eagle-import") (part "MEGA128-A"))
    )
    (comp (ref "Q3")
      (value "26MHz")
      (footprint "eagle-import:HC49U-V")
      (libsource (lib "eagle-import") (part "CRYSTALHC49U-V"))
    )
    (comp (ref "R33")
      (value "10k")
      (footprint "eagle-import:R0805")
      (libsource (lib "eagle-import") (part "R-EU_R0805"))
    )
    (comp (ref "C1")
      (value "100µF")
      (footprint "eagle-import:153CLV-1010")
      (libsource (lib "eagle-import") (part "CPOL-EU153CLV-1010"))
    )
    (comp (ref "C2")
      (value "100µF")
      (footprint "eagle-import:153CLV-0807")
      (libsource (lib "eagle-import") (part "CPOL-EU153CLV-0807"))
    )
    (comp (ref "C3")
      (value "100µF")
      (footprint "eagle-import:153CLV-0807")
      (libsource (lib "eagle-import") (part "CPOL-EU153CLV-0807"))
    )
    (comp (ref "D1")
      (value "SCHOTTKY-DIODESMD")
      (footprint "eagle-import:SMB")
      (libsource (lib "eagle-import") (part "SCHOTTKY-DIODESMD"))
    )
    (comp (ref "D2")
      (value "SCHOTTKY-DIODESMD")
      (footprint "eagle-import:SMB")
      (libsource (lib "eagle-import") (part "SCHOTTKY-DIODESMD"))
    )
    (comp (ref "GND")
      (value "GND")
      (footprint "eagle-import:GOLDKONTAKT3MM")
      (libsource (lib "eagle-import") (part "GOLDKONTAKT_3MM"))
    )
    (comp (ref "IC3")
      (value "LM2596S")
      (footprint "eagle-import:TO263-5")
      (fields (field (name "MF") "NATIONAL SEMICONDUCTOR") (field (name "MPN") "LM2596S-ADJ/NOPB"))
      (libsource (lib "eagle-import") (part "LM2596S"))
    )
    (comp (ref "IC5")
      (value "LM2596S")
      (footprint "eagle-import:TO263-5")
      (fields (field (name "MF") "NATIONAL SEMICONDUCTOR") (field (name "MPN") "LM2596S-ADJ/NOPB"))
      (libsource (lib "eagle-import") (part "LM2596S"))
    )
    (comp (ref "L1")
      (value "100µH")
      (footprint "eagle-import:MSS7341")
      (libsource (lib "eagle-import") (part "MSS7341"))
    )
    (comp (ref "L2")
      (value "100µH")
      (footprint "eagle-import:MSS7341")
      (libsource (lib "eagle-import") (part "MSS7341"))
    )
    (comp (ref "LED1")
      (value "LEDCHIPLED_0805")
      (footprint "eagle-import:CHIPLED_0805")
      (libsource (lib "eagle-import") (part "LEDCHIPLED_0805"))
    )
    (comp (ref "LED2")
      (value "LEDCHIPLED_0805")
      (footprint "eagle-import:CHIPLED_0805")
      (libsource (lib "eagle-import") (part "LEDCHIPLED_0805"))
    )
    (comp (ref "R27")
      (value "R-EU_R0805")
      (footprint "eagle-import:R0805")
      (libsource (lib "eagle-import") (part "R-EU_R0805"))
    )
    (comp (ref "R28")
      (value "R-EU_R0805")
      (footprint "eagle-import:R0805")
      (libsource (lib "eagle-import") (part "R-EU_R0805"))
    )
    (comp (ref "R30")
      (value "R-EU_R0805")
      (footprint "eagle-import:R0805")
      (libsource (lib "eagle-import") (part "R-EU_R0805"))
    )
    (comp (ref "R31")
      (value "R-EU_R0805")
      (footprint "eagle-import:R0805")
      (libsource (lib "eagle-import") (part "R-EU_R0805"))
    )
    (comp (ref "R34")
      (value "180")
      (footprint "eagle-import:R0805")
      (libsource (lib "eagle-import") (part "R-EU_R0805"))
    )
    (comp (ref "R35")
      (value "100")
      (footprint "eagle-import:R0805")
      (libsource (lib "eagle-import") (part "R-EU_R0805"))
    )
    (comp (ref "VCC")
      (value "11.1V")
      (footprint "eagle-import:GOLDKONTAKT3MM")
      (libsource (lib "eagle-import") (part "GOLDKONTAKT_3MM"))
    )
    (comp (ref "C37")
      (value "100n")
      (footprint "eagle-import:C0805")
      (libsource (lib "eagle-import") (part "C-EUC0805"))
    )
    (comp (ref "C38")
      (value "100n")
      (footprint "eagle-import:C0805")
      (libsource (lib "eagle-import") (part "C-EUC0805"))
    )
    (comp (ref "C39")
      (value "100n")
      (footprint "eagle-import:C0805")
      (libsource (lib "eagle-import") (part "C-EUC0805"))
    )
    (comp (ref "R67")
      (value "4k7")
      (footprint "eagle-import:R0805")
      (libsource (lib "eagle-import") (part "R-EU_R0805"))
    )
    (comp (ref "R68")
      (value "4k7")
      (footprint "eagle-import:R0805")
      (libsource (lib "eagle-import") (part "R-EU_R0805"))
    )
    (comp (ref "R69")
      (value "4k7")
      (footprint "eagle-import:R0805")
      (libsource (lib "eagle-import") (part "R-EU_R0805"))
    )
    (comp (ref "R70")
      (value "4k7")
      (footprint "eagle-import:R0805")
      (libsource (lib "eagle-import") (part "R-EU_R0805"))
    )
    (comp (ref "R71")
      (value "4k7")
      (footprint "eagle-import:R0805")
      (libsource (lib "eagle-import") (part "R-EU_R0805"))
    )
    (comp (ref "R72")
      (value "4k7")
      (footprint "eagle-import:R0805")
      (libsource (lib "eagle-import") (part "R-EU_R0805"))
    )
    (comp (ref "R73")
      (value "4k7")
      (footprint "eagle-import:R0805")
      (libsource (lib "eagle-import") (part "R-EU_R0805"))
    )
    (comp (ref "R74")
      (value "4k7")
      (footprint "eagle-import:R0805")
      (libsource (lib "eagle-import") (part "R-EU_R0805"))
    )
    (comp (ref "R75")
      (value "4k7")
      (footprint "eagle-import:R0805")
      (libsource (lib "eagle-import") (part "R-EU_R0805"))
    )
    (comp (ref "LED3")
      (value "LEDKA-3528ASYC")
      (footprint "eagle-import:KA-3528ASYC")
      (libsource (lib "eagle-import") (part "LEDKA-3528ASYC"))
    )
    (comp (ref "LED4")
      (value "LEDKA-3528ASYC")
      (footprint "eagle-import:KA-3528ASYC")
      (libsource (lib "eagle-import") (part "LEDKA-3528ASYC"))
    )
    (comp (ref "LED5")
      (value "LEDKA-3528ASYC")
      (footprint "eagle-import:KA-3528ASYC")
      (libsource (lib "eagle-import") (part "LEDKA-3528ASYC"))
    )
    (comp (ref "LED6")
      (value "LEDKA-3528ASYC")
      (footprint "eagle-import:KA-3528ASYC")
      (libsource (lib "eagle-import") (part "LEDKA-3528ASYC"))
    )
    (comp (ref "LED7")
      (value "LEDKA-3528ASYC")
      (footprint "eagle-import:KA-3528ASYC")
      (libsource (lib "eagle-import") (part "LEDKA-3528ASYC"))
    )
    (comp (ref "LED8")
      (value "LEDKA-3528ASYC")
      (footprint "eagle-import:KA-3528ASYC")
      (libsource (lib "eagle-import") (part "LEDKA-3528ASYC"))
    )
    (comp (ref "LED9")
      (value "LEDCHIP-LED0805")
      (footprint "eagle-import:CHIP-LED0805")
      (libsource (lib "eagle-import") (part "LEDCHIP-LED0805"))
    )
    (comp (ref "LED10")
      (value "LEDCHIP-LED0805")
      (footprint "eagle-import:CHIP-LED0805")
      (libsource (lib "eagle-import") (part "LEDCHIP-LED0805"))
    )
    (comp (ref "LED11")
      (value "LEDCHIP-LED0805")
      (footprint "eagle-import:CHIP-LED0805")
      (libsource (lib "eagle-import") (part "LEDCHIP-LED0805"))
    )
    (comp (ref "LED12")
      (value "LEDCHIP-LED0805")
      (footprint "eagle-import:CHIP-LED0805")
      (libsource (lib "eagle-import") (part "LEDCHIP-LED0805"))
    )
    (comp (ref "LED13")
      (value "LEDCHIP-LED0805")
      (footprint "eagle-import:CHIP-LED0805")
      (libsource (lib "eagle-import") (part "LEDCHIP-LED0805"))
    )
    (comp (ref "LED14")
      (value "LEDCHIP-LED0805")
      (footprint "eagle-import:CHIP-LED0805")
      (libsource (lib "eagle-import") (part "LEDCHIP-LED0805"))
    )
    (comp (ref "PH1")
      (value "LEDKA-3528ASYC")
      (footprint "eagle-import:KA-3528ASYC")
      (libsource (lib "eagle-import") (part "LEDKA-3528ASYC"))
    )
    (comp (ref "PH2")
      (value "LEDKA-3528ASYC")
      (footprint "eagle-import:KA-3528ASYC")
      (libsource (lib "eagle-import") (part "LEDKA-3528ASYC"))
    )
    (comp (ref "PH3")
      (value "LEDKA-3528ASYC")
      (footprint "eagle-import:KA-3528ASYC")
      (libsource (lib "eagle-import") (part "LEDKA-3528ASYC"))
    )
    (comp (ref "PH4")
      (value "LEDKA-3528ASYC")
      (footprint "eagle-import:KA-3528ASYC")
      (libsource (lib "eagle-import") (part "LEDKA-3528ASYC"))
    )
    (comp (ref "PH5")
      (value "LEDKA-3528ASYC")
      (footprint "eagle-import:KA-3528ASYC")
      (libsource (lib "eagle-import") (part "LEDKA-3528ASYC"))
    )
    (comp (ref "PH6")
      (value "LEDKA-3528ASYC")
      (footprint "eagle-import:KA-3528ASYC")
      (libsource (lib "eagle-import") (part "LEDKA-3528ASYC"))
    )
    (comp (ref "R29")
      (value "100")
      (footprint "eagle-import:R0805")
      (libsource (lib "eagle-import") (part "R-EU_R0805"))
    )
    (comp (ref "R32")
      (value "100")
      (footprint "eagle-import:R0805")
      (libsource (lib "eagle-import") (part "R-EU_R0805"))
    )
    (comp (ref "R36")
      (value "100")
      (footprint "eagle-import:R0805")
      (libsource (lib "eagle-import") (part "R-EU_R0805"))
    )
    (comp (ref "R37")
      (value "100")
      (footprint "eagle-import:R0805")
      (libsource (lib "eagle-import") (part "R-EU_R0805"))
    )
    (comp (ref "R38")
      (value "100")
      (footprint "eagle-import:R0805")
      (libsource (lib "eagle-import") (part "R-EU_R0805"))
    )
    (comp (ref "R39")
      (value "100")
      (footprint "eagle-import:R0805")
      (libsource (lib "eagle-import") (part "R-EU_R0805"))
    )
    (comp (ref "R40")
      (value "R-EU_R0805")
      (footprint "eagle-import:R0805")
      (libsource (lib "eagle-import") (part "R-EU_R0805"))
    )
    (comp (ref "R41")
      (value "R-EU_R0805")
      (footprint "eagle-import:R0805")
      (libsource (lib "eagle-import") (part "R-EU_R0805"))
    )
    (comp (ref "R42")
      (value "R-EU_R0805")
      (footprint "eagle-import:R0805")
      (libsource (lib "eagle-import") (part "R-EU_R0805"))
    )
    (comp (ref "R43")
      (value "R-EU_R0805")
      (footprint "eagle-import:R0805")
      (libsource (lib "eagle-import") (part "R-EU_R0805"))
    )
    (comp (ref "R44")
      (value "R-EU_R0805")
      (footprint "eagle-import:R0805")
      (libsource (lib "eagle-import") (part "R-EU_R0805"))
    )
    (comp (ref "R45")
      (value "R-EU_R0805")
      (footprint "eagle-import:R0805")
      (libsource (lib "eagle-import") (part "R-EU_R0805"))
    )
    (comp (ref "R46")
      (value "R-EU_R0805")
      (footprint "eagle-import:R0805")
      (libsource (lib "eagle-import") (part "R-EU_R0805"))
    )
    (comp (ref "R47")
      (value "R-EU_R0805")
      (footprint "eagle-import:R0805")
      (libsource (lib "eagle-import") (part "R-EU_R0805"))
    )
    (comp (ref "R48")
      (value "R-EU_R0805")
      (footprint "eagle-import:R0805")
      (libsource (lib "eagle-import") (part "R-EU_R0805"))
    )
    (comp (ref "R49")
      (value "R-EU_R0805")
      (footprint "eagle-import:R0805")
      (libsource (lib "eagle-import") (part "R-EU_R0805"))
    )
    (comp (ref "R50")
      (value "R-EU_R0805")
      (footprint "eagle-import:R0805")
      (libsource (lib "eagle-import") (part "R-EU_R0805"))
    )
    (comp (ref "R51")
      (value "R-EU_R0805")
      (footprint "eagle-import:R0805")
      (libsource (lib "eagle-import") (part "R-EU_R0805"))
    )
    (comp (ref "R52")
      (value "100")
      (footprint "eagle-import:R0805")
      (libsource (lib "eagle-import") (part "R-EU_R0805"))
    )
    (comp (ref "R53")
      (value "100")
      (footprint "eagle-import:R0805")
      (libsource (lib "eagle-import") (part "R-EU_R0805"))
    )
    (comp (ref "R54")
      (value "100")
      (footprint "eagle-import:R0805")
      (libsource (lib "eagle-import") (part "R-EU_R0805"))
    )
    (comp (ref "R55")
      (value "100")
      (footprint "eagle-import:R0805")
      (libsource (lib "eagle-import") (part "R-EU_R0805"))
    )
    (comp (ref "R56")
      (value "100")
      (footprint "eagle-import:R0805")
      (libsource (lib "eagle-import") (part "R-EU_R0805"))
    )
    (comp (ref "R57")
      (value "100")
      (footprint "eagle-import:R0805")
      (libsource (lib "eagle-import") (part "R-EU_R0805"))
    )
  )
  (nets
    (net (code "1") (name "+3V3") (class "Default")
      (node (ref "C3") (pin "+") (pinfunction "+_+") (pintype "passive"))
      (node (ref "C4") (pin "1") (pinfunction "1_1") (pintype "passive"))
      (node (ref "C5") (pin "1") (pinfunction "1_1") (pintype "passive"))
      (node (ref "C6") (pin "1") (pinfunction "1_1") (pintype "passive"))
      (node (ref "C7") (pin "1") (pinfunction "1_1") (pintype "passive"))
      (node (ref "C8") (pin "1") (pinfunction "1_1") (pintype "passive"))
      (node (ref "C9") (pin "1") (pinfunction "1_1") (pintype "passive"))
      (node (ref "IC2") (pin "21") (pinfunction "VCC_21") (pintype "power_in"))
      (node (ref "IC2") (pin "52") (pinfunction "VCC_52") (pintype "power_in"))
      (node (ref "IC2") (pin "64") (pinfunction "AVCC_64") (pintype "power_in"))
      (node (ref "L2") (pin "2") (pinfunction "2_2") (pintype "passive"))
      (node (ref "R29") (pin "2") (pinfunction "2_2") (pintype "passive"))
      (node (ref "R30") (pin "2") (pinfunction "2_2") (pintype "passive"))
      (node (ref "R32") (pin "2") (pinfunction "2_2") (pintype "passive"))
      (node (ref "R33") (pin "2") (pinfunction "2_2") (pintype "passive"))
      (node (ref "R35") (pin "2") (pinfunction "2_2") (pintype "passive"))
      (node (ref "R36") (pin "2") (pinfunction "2_2") (pintype "passive"))
      (node (ref "R37") (pin "2") (pinfunction "2_2") (pintype "passive"))
      (node (ref "R38") (pin "2") (pinfunction "2_2") (pintype "passive"))
      (node (ref "R39") (pin "2") (pinfunction "2_2") (pintype "passive"))
      (node (ref "R40") (pin "2") (pinfunction "2_2") (pintype "passive"))
      (node (ref "R41") (pin "2") (pinfunction "2_2") (pintype "passive"))
      (node (ref "R42") (pin "2") (pinfunction "2_2") (pintype "passive"))
      (node (ref "R43") (pin "2") (pinfunction "2_2") (pintype "passive"))
      (node (ref "R44") (pin "2") (pinfunction "2_2") (pintype "passive"))
      (node (ref "R45") (pin "2") (pinfunction "2_2") (pintype "passive"))
    )
    (net (code "2") (name "+5V") (class "Default")
      (node (ref "C15") (pin "1") (pinfunction "1_1") (pintype "passive"))
      (node (ref "C16") (pin "1") (pinfunction "1_1") (pintype "passive"))
      (node (ref "C17") (pin "1") (pinfunction "1_1") (pintype "passive"))
      (node (ref "C18") (pin "1") (pinfunction "1_1") (pintype "passive"))
      (node (ref "C19") (pin "1") (pinfunction "1_1") (pintype "passive"))
      (node (ref "C2") (pin "+") (pinfunction "+_+") (pintype "passive"))
      (node (ref "C20") (pin "1") (pinfunction "1_1") (pintype "passive"))
      (node (ref "C26") (pin "1") (pinfunction "1_1") (pintype "passive"))
      (node (ref "C27") (pin "1") (pinfunction "1_1") (pintype "passive"))
      (node (ref "C28") (pin "1") (pinfunction "1_1") (pintype "passive"))
      (node (ref "C29") (pin "1") (pinfunction "1_1") (pintype "passive"))
      (node (ref "C30") (pin "1") (pinfunction "1_1") (pintype "passive"))
      (node (ref "C31") (pin "1") (pinfunction "1_1") (pintype "passive"))
      (node (ref "IC1") (pin "18") (pinfunction "AVCC_18") (pintype "power_in"))
      (node (ref "IC1") (pin "4") (pinfunction "VCC_4") (pintype "power_in"))
      (node (ref "IC1") (pin "6") (pinfunction "VCC_6") (pintype "power_in"))
      (node (ref "IC4") (pin "18") (pinfunction "AVCC_18") (pintype "power_in"))
      (node (ref "IC4") (pin "4") (pinfunction "VCC_4") (pintype "power_in"))
      (node (ref "IC4") (pin "6") (pinfunction "VCC_6") (pintype "power_in"))
      (node (ref "L1") (pin "2") (pinfunction "2_2") (pintype "passive"))
      (node (ref "R13") (pin "2") (pinfunction "2_2") (pintype "passive"))
      (node (ref "R14") (pin "2") (pinfunction "2_2") (pintype "passive"))
      (node (ref "R27") (pin "2") (pinfunction "2_2") (pintype "passive"))
      (node (ref "R34") (pin "2") (pinfunction "2_2") (pintype "passive"))
    )
    (net (code "3") (name "1_A") (class "Default")
      (node (ref "1_A") (pin "1") (pinfunction "1_1") (pintype "bidirectional"))
      (node (ref "R58") (pin "2") (pinfunction "2_2") (pintype "passive"))
      (node (ref "U2") (pin "5") (pinfunction "D_5") (pintype "bidirectional"))
      (node (ref "U2") (pin "6#") (pinfunction "D_6#") (pintype "bidirectional"))
      (node (ref "U2") (pin "7") (pinfunction "D_7") (pintype "bidirectional"))
      (node (ref "U2") (pin "8") (pinfunction "D_8") (pintype "bidirectional"))
      (node (ref "U5") (pin "5") (pinfunction "D_5") (pintype "bidirectional"))
      (node (ref "U5") (pin "6#") (pinfunction "D_6#") (pintype "bidirectional"))
      (node (ref "U5") (pin "7") (pinfunction "D_7") (pintype "bidirectional"))
      (node (ref "U5") (pin "8") (pinfunction "D_8") (pintype "bidirectional"))
    )
    (net (code "4") (name "1_A_EMF") (class "Default")
      (node (ref "C10") (pin "1") (pinfunction "1_1") (pintype "passive"))
      (node (ref "R58") (pin "1") (pinfunction "1_1") (pintype "passive"))
      (node (ref "R59") (pin "2") (pinfunction "2_2") (pintype "passive"))
      (node (ref "R64") (pin "2") (pinfunction "2_2") (pintype "passive"))
    )
    (net (code "5") (name "1_B") (class "Default")
      (node (ref "1_B") (pin "1") (pinfunction "1_1") (pintype "bidirectional"))
      (node (ref "R60") (pin "2") (pinfunction "2_2") (pintype "passive"))
      (node (ref "U3") (pin "5") (pinfunction "D_5") (pintype "bidirectional"))
      (node (ref "U3") (pin "6#") (pinfunction "D_6#") (pintype "bidirectional"))
      (node (ref "U3") (pin "7") (pinfunction "D_7") (pintype "bidirectional"))
      (node (ref "U3") (pin "8") (pinfunction "D_8") (pintype "bidirectional"))
      (node (ref "U6") (pin "5") (pinfunction "D_5") (pintype "bidirectional"))
      (node (ref "U6") (pin "6#") (pinfunction "D_6#") (pintype "bidirectional"))
      (node (ref "U6") (pin "7") (pinfunction "D_7") (pintype "bidirectional"))
      (node (ref "U6") (pin "8") (pinfunction "D_8") (pintype "bidirectional"))
    )
    (net (code "6") (name "1_B_EMF") (class "Default")
      (node (ref "C11") (pin "1") (pinfunction "1_1") (pintype "passive"))
      (node (ref "R60") (pin "1") (pinfunction "1_1") (pintype "passive"))
      (node (ref "R61") (pin "2") (pinfunction "2_2") (pintype "passive"))
      (node (ref "R65") (pin "2") (pinfunction "2_2") (pintype "passive"))
    )
    (net (code "7") (name "1_C") (class "Default")
      (node (ref "1_C") (pin "1") (pinfunction "1_1") (pintype "bidirectional"))
      (node (ref "R62") (pin "2") (pinfunction "2_2") (pintype "passive"))
      (node (ref "U4") (pin "5") (pinfunction "D_5") (pintype "bidirectional"))
      (node (ref "U4") (pin "6#") (pinfunction "D_6#") (pintype "bidirectional"))
      (node (ref "U4") (pin "7") (pinfunction "D_7") (pintype "bidirectional"))
      (node (ref "U4") (pin "8") (pinfunction "D_8") (pintype "bidirectional"))
      (node (ref "U7") (pin "5") (pinfunction "D_5") (pintype "bidirectional"))
      (node (ref "U7") (pin "6#") (pinfunction "D_6#") (pintype "bidirectional"))
      (node (ref "U7") (pin "7") (pinfunction "D_7") (pintype "bidirectional"))
      (node (ref "U7") (pin "8") (pinfunction "D_8") (pintype "bidirectional"))
    )
    (net (code "8") (name "1_C_EMF") (class "Default")
      (node (ref "C12") (pin "1") (pinfunction "1_1") (pintype "passive"))
      (node (ref "R62") (pin "1") (pinfunction "1_1") (pintype "passive"))
      (node (ref "R63") (pin "2") (pinfunction "2_2") (pintype "passive"))
      (node (ref "R66") (pin "2") (pinfunction "2_2") (pintype "passive"))
    )
    (net (code "9") (name "1_DIR") (class "Default")
      (node (ref "IC2") (pin "29") (pinfunction "(IC1)PD4_29") (pintype "bidirectional"))
      (node (ref "IC4") (pin "31") (pinfunction "PD1(TXD)_31") (pintype "bidirectional"))
    )
    (net (code "10") (name "1_MITTEL") (class "Default")
      (node (ref "R64") (pin "1") (pinfunction "1_1") (pintype "passive"))
      (node (ref "R65") (pin "1") (pinfunction "1_1") (pintype "passive"))
      (node (ref "R66") (pin "1") (pinfunction "1_1") (pintype "passive"))
    )
    (net (code "11") (name "1_N1") (class "Default")
      (node (ref "IC4") (pin "15") (pinfunction "PB3(MOSI/OC2)_15") (pintype "bidirectional"))
      (node (ref "T14") (pin "1") (pinfunction "B_1") (pintype "passive"))
    )
    (net (code "12") (name "1_N2") (class "Default")
      (node (ref "IC4") (pin "16") (pinfunction "PB4(MISO)_16") (pintype "bidirectional"))
      (node (ref "T16") (pin "1") (pinfunction "B_1") (pintype "passive"))
    )
    (net (code "13") (name "1_N3") (class "Default")
      (node (ref "IC4") (pin "17") (pinfunction "PB5(SCK)_17") (pintype "bidirectional"))
      (node (ref "T17") (pin "1") (pinfunction "B_1") (pintype "passive"))
    )
    (net (code "14") (name "1_P1") (class "Default")
      (node (ref "IC4") (pin "14") (pinfunction "PB2(SS/OC1B)_14") (pintype "bidirectional"))
      (node (ref "T13") (pin "1") (pinfunction "B_1") (pintype "passive"))
    )
    (net (code "15") (name "1_P2") (class "Default")
      (node (ref "IC4") (pin "13") (pinfunction "PB1(OC1A)_13") (pintype "bidirectional"))
      (node (ref "T15") (pin "1") (pinfunction "B_1") (pintype "passive"))
    )
    (net (code "16") (name "1_P3") (class "Default")
      (node (ref "IC4") (pin "12") (pinfunction "PB0(ICP)_12") (pintype "bidirectional"))
      (node (ref "T18") (pin "1") (pinfunction "B_1") (pintype "passive"))
    )
    (net (code "17") (name "1_STP") (class "Default")
      (node (ref "IC2") (pin "28") (pinfunction "(TXD1/INT3)PD3_28") (pintype "bidirectional"))
      (node (ref "IC4") (pin "32") (pinfunction "PD2(INT0)_32") (pintype "bidirectional"))
    )
    (net (code "18") (name "2_A") (class "Default")
      (node (ref "2_A") (pin "1") (pinfunction "1_1") (pintype "bidirectional"))
      (node (ref "R67") (pin "2") (pinfunction "2_2") (pintype "passive"))
      (node (ref "U11") (pin "5") (pinfunction "D_5") (pintype "bidirectional"))
      (node (ref "U11") (pin "6#") (pinfunction "D_6#") (pintype "bidirectional"))
      (node (ref "U11") (pin "7") (pinfunction "D_7") (pintype "bidirectional"))
      (node (ref "U11") (pin "8") (pinfunction "D_8") (pintype "bidirectional"))
      (node (ref "U8") (pin "5") (pinfunction "D_5") (pintype "bidirectional"))
      (node (ref "U8") (pin "6#") (pinfunction "D_6#") (pintype "bidirectional"))
      (node (ref "U8") (pin "7") (pinfunction "D_7") (pintype "bidirectional"))
      (node (ref "U8") (pin "8") (pinfunction "D_8") (pintype "bidirectional"))
    )
    (net (code "19") (name "2_A_EMF") (class "Default")
      (node (ref "C37") (pin "1") (pinfunction "1_1") (pintype "passive"))
      (node (ref "R67") (pin "1") (pinfunction "1_1") (pintype "passive"))
      (node (ref "R68") (pin "2") (pinfunction "2_2") (pintype "passive"))
      (node (ref "R73") (pin "2") (pinfunction "2_2") (pintype "passive"))
    )
    (net (code "20") (name "2_B") (class "Default")
      (node (ref "2_B") (pin "1") (pinfunction "1_1") (pintype "bidirectional"))
      (node (ref "R69") (pin "2") (pinfunction "2_2") (pintype "passive"))
      (node (ref "U12") (pin "5") (pinfunction "D_5") (pintype "bidirectional"))
      (node (ref "U12") (pin "6#") (pinfunction "D_6#") (pintype "bidirectional"))
      (node (ref "U12") (pin "7") (pinfunction "D_7") (pintype "bidirectional"))
      (node (ref "U12") (pin "8") (pinfunction "D_8") (pintype "bidirectional"))
      (node (ref "U9") (pin "5") (pinfunction "D_5") (pintype "bidirectional"))
      (node (ref "U9") (pin "6#") (pinfunction "D_6#") (pintype "bidirectional"))
      (node (ref "U9") (pin "7") (pinfunction "D_7") (pintype "bidirectional"))
      (node (ref "U9") (pin "8") (pinfunction "D_8") (pintype "bidirectional"))
    )
    (net (code "21") (name "2_B_EMF") (class "Default")
      (node (ref "C38") (pin "1") (pinfunction "1_1") (pintype "passive"))
      (node (ref "R69") (pin "1") (pinfunction "1_1") (pintype "passive"))
      (node (ref "R70") (pin "2") (pinfunction "2_2") (pintype "passive"))
      (node (ref "R74") (pin "2") (pinfunction "2_2") (pintype "passive"))
    )
    (net (code "22") (name "2_C") (class "Default")
      (node (ref "2_C") (pin "1") (pinfunction "1_1") (pintype "bidirectional"))
      (node (ref "R71") (pin "2") (pinfunction "2_2") (pintype "passive"))
      (node (ref "U10") (pin "5") (pinfunction "D_5") (pintype "bidirectional"))
      (node (ref "U10") (pin "6#") (pinfunction "D_6#") (pintype "bidirectional"))
      (node (ref "U10") (pin "7") (pinfunction "D_7") (pintype "bidirectional"))
      (node (ref "U10") (pin "8") (pinfunction "D_8") (pintype "bidirectional"))
      (node (ref "U13") (pin "5") (pinfunction "D_5") (pintype "bidirectional"))
      (node (ref "U13") (pin "6#") (pinfunction "D_6#") (pintype "bidirectional"))
      (node (ref "U13") (pin "7") (pinfunction "D_7") (pintype "bidirectional"))
      (node (ref "U13") (pin "8") (pinfunction "D_8") (pintype "bidirectional"))
    )
    (net (code "23") (name "2_C_EMF") (class "Default")
      (node (ref "C39") (pin "1") (pinfunction "1_1") (pintype "passive"))
      (node (ref "R71") (pin "1") (pinfunction "1_1") (pintype "passive"))
      (node (ref "R72") (pin "2") (pinfunction "2_2") (pintype "passive"))
      (node (ref "R75") (pin "2") (pinfunction "2_2") (pintype "passive"))
    )
    (net (code "24") (name "2_DIR") (class "Default")
      (node (ref "IC1") (pin "31") (pinfunction "PD1(TXD)_31") (pintype "bidirectional"))
      (node (ref "IC2") (pin "31") (pinfunction "(T1)PD6_31") (pintype "bidirectional"))
    )
    (net (code "25") (name "2_MITTEL") (class "Default")
      (node (ref "R73") (pin "1") (pinfunction "1_1") (pintype "passive"))
      (node (ref "R74") (pin "1") (pinfunction "1_1") (pintype "passive"))
      (node (ref "R75") (pin "1") (pinfunction "1_1") (pintype "passive"))
    )
    (net (code "26") (name "2_N1") (class "Default")
      (node (ref "IC1") (pin "15") (pinfunction "PB3(MOSI/OC2)_15") (pintype "bidirectional"))
      (node (ref "T2") (pin "1") (pinfunction "B_1") (pintype "passive"))
    )
    (net (code "27") (name "2_N2") (class "Default")
      (node (ref "IC1") (pin "16") (pinfunction "PB4(MISO)_16") (pintype "bidirectional"))
      (node (ref "T4") (pin "1") (pinfunction "B_1") (pintype "passive"))
    )
    (net (code "28") (name "2_N3") (class "Default")
      (node (ref "IC1") (pin "17") (pinfunction "PB5(SCK)_17") (pintype "bidirectional"))
      (node (ref "T5") (pin "1") (pinfunction "B_1") (pintype "passive"))
    )
    (net (code "29") (name "2_P1") (class "Default")
      (node (ref "IC1") (pin "14") (pinfunction "PB2(SS/OC1B)_14") (pintype "bidirectional"))
      (node (ref "T1") (pin "1") (pinfunction "B_1") (pintype "passive"))
    )
    (net (code "30") (name "2_P2") (class "Default")
      (node (ref "IC1") (pin "13") (pinfunction "PB1(OC1A)_13") (pintype "bidirectional"))
      (node (ref "T3") (pin "1") (pinfunction "B_1") (pintype "passive"))
    )
    (net (code "31") (name "2_P3") (class "Default")
      (node (ref "IC1") (pin "12") (pinfunction "PB0(ICP)_12") (pintype "bidirectional"))
      (node (ref "T6") (pin "1") (pinfunction "B_1") (pintype "passive"))
    )
    (net (code "32") (name "2_STP") (class "Default")
      (node (ref "IC1") (pin "32") (pinfunction "PD2(INT0)_32") (pintype "bidirectional"))
      (node (ref "IC2") (pin "30") (pinfunction "(XCK1)PD5_30") (pintype "bidirectional"))
    )
    (net (code "33") (name "3V3_FEEDBACK") (class "Default")
      (node (ref "IC3") (pin "4") (pinfunction "FB_4") (pintype "input"))
      (node (ref "R30") (pin "1") (pinfunction "1_1") (pintype "passive"))
      (node (ref "R31") (pin "2") (pinfunction "2_2") (pintype "passive"))
    )
    (net (code "34") (name "5V_FEEDBACK") (class "Default")
      (node (ref "IC5") (pin "4") (pinfunction "FB_4") (pintype "input"))
      (node (ref "R27") (pin "1") (pinfunction "1_1") (pintype "passive"))
      (node (ref "R28") (pin "2") (pinfunction "2_2") (pintype "passive"))
    )
    (net (code "35") (name "GND") (class "Default")
      (node (ref "C1") (pin "-") (pinfunction "-_-") (pintype "passive"))
      (node (ref "C10") (pin "2") (pinfunction "2_2") (pintype "passive"))
      (node (ref "C11") (pin "2") (pinfunction "2_2") (pintype "passive"))
      (node (ref "C12") (pin "2") (pinfunction "2_2") (pintype "passive"))
      (node (ref "C13") (pin "2") (pinfunction "2_2") (pintype "passive"))
      (node (ref "C14") (pin "1") (pinfunction "1_1") (pintype "passive"))
      (node (ref "C15") (pin "2") (pinfunction "2_2") (pintype "passive"))
      (node (ref "C16") (pin "2") (pinfunction "2_2") (pintype "passive"))
      (node (ref "C17") (pin "2") (pinfunction "2_2") (pintype "passive"))
      (node (ref "C18") (pin "2") (pinfunction "2_2") (pintype "passive"))
      (node (ref "C19") (pin "2") (pinfunction "2_2") (pintype "passive"))
      (node (ref "C2") (pin "-") (pinfunction "-_-") (pintype "passive"))
      (node (ref "C20") (pin "2") (pinfunction "2_2") (pintype "passive"))
      (node (ref "C21") (pin "2") (pinfunction "2_2") (pintype "passive"))
      (node (ref "C22") (pin "2") (pinfunction "2_2") (pintype "passive"))
      (node (ref "C23") (pin "2") (pinfunction "2_2") (pintype "passive"))
      (node (ref "C24") (pin "2") (pinfunction "2_2") (pintype "passive"))
      (node (ref "C25") (pin "1") (pinfunction "1_1") (pintype "passive"))
      (node (ref "C26") (pin "2") (pinfunction "2_2") (pintype "passive"))
      (node (ref "C27") (pin "2") (pinfunction "2_2") (pintype "passive"))
      (node (ref "C28") (pin "2") (pinfunction "2_2") (pintype "passive"))
      (node (ref "C29") (pin "2") (pinfunction "2_2") (pintype "passive"))
      (node (ref "C3") (pin "-") (pinfunction "-_-") (pintype "passive"))
      (node (ref "C30") (pin "2") (pinfunction "2_2") (pintype "passive"))
      (node (ref "C31") (pin "2") (pinfunction "2_2") (pintype "passive"))
      (node (ref "C32") (pin "2") (pinfunction "2_2") (pintype "passive"))
      (node (ref "C33") (pin "2") (pinfunction "2_2") (pintype "passive"))
      (node (ref "C34") (pin "2") (pinfunction "2_2") (pintype "passive"))
      (node (ref "C35") (pin "2") (pinfunction "2_2") (pintype "passive"))
      (node (ref "C36") (pin "1") (pinfunction "1_1") (pintype "passive"))
      (node (ref "C37") (pin "2") (pinfunction "2_2") (pintype "passive"))
      (node (ref "C38") (pin "2") (pinfunction "2_2") (pintype "passive"))
      (node (ref "C39") (pin "2") (pinfunction "2_2") (pintype "passive"))
      (node (ref "C4") (pin "2") (pinfunction "2_2") (pintype "passive"))
      (node (ref "C5") (pin "2") (pinfunction "2_2") (pintype "passive"))
      (node (ref "C6") (pin "2") (pinfunction "2_2") (pintype "passive"))
      (node (ref "C7") (pin "2") (pinfunction "2_2") (pintype "passive"))
      (node (ref "C8") (pin "2") (pinfunction "2_2") (pintype "passive"))
      (node (ref "C9") (pin "2") (pinfunction "2_2") (pintype "passive"))
      (node (ref "D1") (pin "A") (pinfunction "A_A") (pintype "passive"))
      (node (ref "D2") (pin "A") (pinfunction "A_A") (pintype "passive"))
      (node (ref "GND") (pin "1") (pinfunction "1_1") (pintype "bidirectional"))
      (node (ref "IC1") (pin "21") (pinfunction "GND_21") (pintype "power_in"))
      (node (ref "IC1") (pin "3") (pinfunction "GND_3") (pintype "power_in"))
      (node (ref "IC1") (pin "5") (pinfunction "GND_5") (pintype "power_in"))
      (node (ref "IC2") (pin "22") (pinfunction "GND_22") (pintype "power_in"))
      (node (ref "IC2") (pin "53") (pinfunction "GND_53") (pintype "power_in"))
      (node (ref "IC2") (pin "63") (pinfunction "GND_63") (pintype "power_in"))
      (node (ref "IC3") (pin "3") (pinfunction "GND_3") (pintype "power_in"))
      (node (ref "IC3") (pin "5") (pinfunction "~{ON}/OFF_5") (pintype "input"))
      (node (ref "IC4") (pin "21") (pinfunction "GND_21") (pintype "power_in"))
      (node (ref "IC4") (pin "3") (pinfunction "GND_3") (pintype "power_in"))
      (node (ref "IC4") (pin "5") (pinfunction "GND_5") (pintype "power_in"))
      (node (ref "IC5") (pin "3") (pinfunction "GND_3") (pintype "power_in"))
      (node (ref "IC5") (pin "5") (pinfunction "~{ON}/OFF_5") (pintype "input"))
      (node (ref "LED1") (pin "C") (pinfunction "C_C") (pintype "passive"))
      (node (ref "LED2") (pin "C") (pinfunction "C_C") (pintype "passive"))
      (node (ref "LED3") (pin "C") (pinfunction "C_C") (pintype "passive"))
      (node (ref "LED4") (pin "C") (pinfunction "C_C") (pintype "passive"))
      (node (ref "LED5") (pin "C") (pinfunction "C_C") (pintype "passive"))
      (node (ref "LED6") (pin "C") (pinfunction "C_C") (pintype "passive"))
      (node (ref "LED7") (pin "C") (pinfunction "C_C") (pintype "passive"))
      (node (ref "LED8") (pin "C") (pinfunction "C_C") (pintype "passive"))
      (node (ref "R28") (pin "1") (pinfunction "1_1") (pintype "passive"))
      (node (ref "R31") (pin "1") (pinfunction "1_1") (pintype "passive"))
      (node (ref "R46") (pin "1") (pinfunction "1_1") (pintype "passive"))
      (node (ref "R47") (pin "1") (pinfunction "1_1") (pintype "passive"))
      (node (ref "R48") (pin "1") (pinfunction "1_1") (pintype "passive"))
      (node (ref "R49") (pin "1") (pinfunction "1_1") (pintype "passive"))
      (node (ref "R50") (pin "1") (pinfunction "1_1") (pintype "passive"))
      (node (ref "R51") (pin "1") (pinfunction "1_1") (pintype "passive"))
      (node (ref "R52") (pin "1") (pinfunction "1_1") (pintype "passive"))
      (node (ref "R53") (pin "1") (pinfunction "1_1") (pintype "passive"))
      (node (ref "R54") (pin "1") (pinfunction "1_1") (pintype "passive"))
      (node (ref "R55") (pin "1") (pinfunction "1_1") (pintype "passive"))
      (node (ref "R56") (pin "1") (pinfunction "1_1") (pintype "passive"))
      (node (ref "R57") (pin "1") (pinfunction "1_1") (pintype "passive"))
      (node (ref "R59") (pin "1") (pinfunction "1_1") (pintype "passive"))
      (node (ref "R61") (pin "1") (pinfunction "1_1") (pintype "passive"))
      (node (ref "R63") (pin "1") (pinfunction "1_1") (pintype "passive"))
      (node (ref "R68") (pin "1") (pinfunction "1_1") (pintype "passive"))
      (node (ref "R70") (pin "1") (pinfunction "1_1") (pintype "passive"))
      (node (ref "R72") (pin "1") (pinfunction "1_1") (pintype "passive"))
      (node (ref "T1") (pin "2") (pinfunction "E_2") (pintype "passive"))
      (node (ref "T13") (pin "2") (pinfunction "E_2") (pintype "passive"))
      (node (ref "T14") (pin "2") (pinfunction "E_2") (pintype "passive"))
      (node (ref "T15") (pin "2") (pinfunction "E_2") (pintype "passive"))
      (node (ref "T16") (pin "2") (pinfunction "E_2") (pintype "passive"))
      (node (ref "T17") (pin "2") (pinfunction "E_2") (pintype "passive"))
      (node (ref "T18") (pin "2") (pinfunction "E_2") (pintype "passive"))
      (node (ref "T2") (pin "2") (pinfunction "E_2") (pintype "passive"))
      (node (ref "T3") (pin "2") (pinfunction "E_2") (pintype "passive"))
      (node (ref "T4") (pin "2") (pinfunction "E_2") (pintype "passive"))
      (node (ref "T5") (pin "2") (pinfunction "E_2") (pintype "passive"))
      (node (ref "T6") (pin "2") (pinfunction "E_2") (pintype "passive"))
      (node (ref "U11") (pin "1") (pinfunction "S_1") (pintype "bidirectional"))
      (node (ref "U11") (pin "2") (pinfunction "S_2") (pintype "bidirectional"))
      (node (ref "U11") (pin "3") (pinfunction "S_3") (pintype "bidirectional"))
      (node (ref "U12") (pin "1") (pinfunction "S_1") (pintype "bidirectional"))
      (node (ref "U12") (pin "2") (pinfunction "S_2") (pintype "bidirectional"))
      (node (ref "U12") (pin "3") (pinfunction "S_3") (pintype "bidirectional"))
      (node (ref "U13") (pin "1") (pinfunction "S_1") (pintype "bidirectional"))
      (node (ref "U13") (pin "2") (pinfunction "S_2") (pintype "bidirectional"))
      (node (ref "U13") (pin "3") (pinfunction "S_3") (pintype "bidirectional"))
      (node (ref "U5") (pin "1") (pinfunction "S_1") (pintype "bidirectional"))
      (node (ref "U5") (pin "2") (pinfunction "S_2") (pintype "bidirectional"))
      (node (ref "U5") (pin "3") (pinfunction "S_3") (pintype "bidirectional"))
      (node (ref "U6") (pin "1") (pinfunction "S_1") (pintype "bidirectional"))
      (node (ref "U6") (pin "2") (pinfunction "S_2") (pintype "bidirectional"))
      (node (ref "U6") (pin "3") (pinfunction "S_3") (pintype "bidirectional"))
      (node (ref "U7") (pin "1") (pinfunction "S_1") (pintype "bidirectional"))
      (node (ref "U7") (pin "2") (pinfunction "S_2") (pintype "bidirectional"))
      (node (ref "U7") (pin "3") (pinfunction "S_3") (pintype "bidirectional"))
    )
    (net (code "36") (name "Net-(IC1-PB6(XTAL1{slash}TOSC1))") (class "Default")
      (node (ref "C25") (pin "2") (pinfunction "2_2") (pintype "passive"))
      (node (ref "IC1") (pin "7") (pinfunction "PB6(XTAL1/TOSC1)_7") (pintype "bidirectional"))
      (node (ref "Q2") (pin "2") (pinfunction "2_2") (pintype "passive"))
    )
    (net (code "37") (name "Net-(IC1-PB7(XTAL2{slash}TOSC2))") (class "Default")
      (node (ref "C24") (pin "1") (pinfunction "1_1") (pintype "passive"))
      (node (ref "IC1") (pin "8") (pinfunction "PB7(XTAL2/TOSC2)_8") (pintype "bidirectional"))
      (node (ref "Q2") (pin "1") (pinfunction "1_1") (pintype "passive"))
    )
    (net (code "38") (name "Net-(IC1-PC6({slash}RESET))") (class "Default")
      (node (ref "IC1") (pin "29") (pinfunction "PC6(/RESET)_29") (pintype "bidirectional"))
      (node (ref "R14") (pin "1") (pinfunction "1_1") (pintype "passive"))
    )
    (net (code "39") (name "Net-(IC2-RESET)") (class "Default")
      (node (ref "IC2") (pin "20") (pinfunction "RESET_20") (pintype "input"))
      (node (ref "R33") (pin "1") (pinfunction "1_1") (pintype "passive"))
    )
    (net (code "40") (name "Net-(IC2-XTAL1)") (class "Default")
      (node (ref "C35") (pin "1") (pinfunction "1_1") (pintype "passive"))
      (node (ref "IC2") (pin "24") (pinfunction "XTAL1_24") (pintype "bidirectional"))
      (node (ref "Q3") (pin "1") (pinfunction "1_1") (pintype "passive"))
    )
    (net (code "41") (name "Net-(IC2-XTAL2)") (class "Default")
      (node (ref "C36") (pin "2") (pinfunction "2_2") (pintype "passive"))
      (node (ref "IC2") (pin "23") (pinfunction "XTAL2_23") (pintype "bidirectional"))
      (node (ref "Q3") (pin "2") (pinfunction "2_2") (pintype "passive"))
    )
    (net (code "42") (name "Net-(IC3-OUT)") (class "Default")
      (node (ref "D2") (pin "C") (pinfunction "C_C") (pintype "passive"))
      (node (ref "IC3") (pin "2") (pinfunction "OUT_2") (pintype "output"))
      (node (ref "L2") (pin "1") (pinfunction "1_1") (pintype "passive"))
    )
    (net (code "43") (name "Net-(IC4-PB6(XTAL1{slash}TOSC1))") (class "Default")
      (node (ref "C14") (pin "2") (pinfunction "2_2") (pintype "passive"))
      (node (ref "IC4") (pin "7") (pinfunction "PB6(XTAL1/TOSC1)_7") (pintype "bidirectional"))
      (node (ref "Q1") (pin "2") (pinfunction "2_2") (pintype "passive"))
    )
    (net (code "44") (name "Net-(IC4-PB7(XTAL2{slash}TOSC2))") (class "Default")
      (node (ref "C13") (pin "1") (pinfunction "1_1") (pintype "passive"))
      (node (ref "IC4") (pin "8") (pinfunction "PB7(XTAL2/TOSC2)_8") (pintype "bidirectional"))
      (node (ref "Q1") (pin "1") (pinfunction "1_1") (pintype "passive"))
    )
    (net (code "45") (name "Net-(IC4-PC6({slash}RESET))") (class "Default")
      (node (ref "IC4") (pin "29") (pinfunction "PC6(/RESET)_29") (pintype "bidirectional"))
      (node (ref "R13") (pin "1") (pinfunction "1_1") (pintype "passive"))
    )
    (net (code "46") (name "Net-(IC5-OUT)") (class "Default")
      (node (ref "D1") (pin "C") (pinfunction "C_C") (pintype "passive"))
      (node (ref "IC5") (pin "2") (pinfunction "OUT_2") (pintype "output"))
      (node (ref "L1") (pin "1") (pinfunction "1_1") (pintype "passive"))
    )
    (net (code "47") (name "Net-(LED1-PadA)") (class "Default")
      (node (ref "LED1") (pin "A") (pinfunction "A_A") (pintype "passive"))
      (node (ref "R34") (pin "1") (pinfunction "1_1") (pintype "passive"))
    )
    (net (code "48") (name "Net-(LED2-PadA)") (class "Default")
      (node (ref "LED2") (pin "A") (pinfunction "A_A") (pintype "passive"))
      (node (ref "R35") (pin "1") (pinfunction "1_1") (pintype "passive"))
    )
    (net (code "49") (name "Net-(LED3-PadA)") (class "Default")
      (node (ref "LED3") (pin "A") (pinfunction "A_A") (pintype "passive"))
      (node (ref "R29") (pin "1") (pinfunction "1_1") (pintype "passive"))
    )
    (net (code "50") (name "Net-(LED4-PadA)") (class "Default")
      (node (ref "LED4") (pin "A") (pinfunction "A_A") (pintype "passive"))
      (node (ref "R32") (pin "1") (pinfunction "1_1") (pintype "passive"))
    )
    (net (code "51") (name "Net-(LED5-PadA)") (class "Default")
      (node (ref "LED5") (pin "A") (pinfunction "A_A") (pintype "passive"))
      (node (ref "R36") (pin "1") (pinfunction "1_1") (pintype "passive"))
    )
    (net (code "52") (name "Net-(LED6-PadA)") (class "Default")
      (node (ref "LED6") (pin "A") (pinfunction "A_A") (pintype "passive"))
      (node (ref "R37") (pin "1") (pinfunction "1_1") (pintype "passive"))
    )
    (net (code "53") (name "Net-(LED7-PadA)") (class "Default")
      (node (ref "LED7") (pin "A") (pinfunction "A_A") (pintype "passive"))
      (node (ref "R38") (pin "1") (pinfunction "1_1") (pintype "passive"))
    )
    (net (code "54") (name "Net-(LED8-PadA)") (class "Default")
      (node (ref "LED8") (pin "A") (pinfunction "A_A") (pintype "passive"))
      (node (ref "R39") (pin "1") (pinfunction "1_1") (pintype "passive"))
    )
    (net (code "55") (name "Net-(LED9-PadC)") (class "Default")
      (node (ref "LED9") (pin "C") (pinfunction "C_C") (pintype "passive"))
      (node (ref "R52") (pin "2") (pinfunction "2_2") (pintype "passive"))
    )
    (net (code "56") (name "Net-(LED10-PadC)") (class "Default")
      (node (ref "LED10") (pin "C") (pinfunction "C_C") (pintype "passive"))
      (node (ref "R53") (pin "2") (pinfunction "2_2") (pintype "passive"))
    )
    (net (code "57") (name "Net-(LED11-PadC)") (class "Default")
      (node (ref "LED11") (pin "C") (pinfunction "C_C") (pintype "passive"))
      (node (ref "R54") (pin "2") (pinfunction "2_2") (pintype "passive"))
    )
    (net (code "58") (name "Net-(LED12-PadC)") (class "Default")
      (node (ref "LED12") (pin "C") (pinfunction "C_C") (pintype "passive"))
      (node (ref "R55") (pin "2") (pinfunction "2_2") (pintype "passive"))
    )
    (net (code "59") (name "Net-(LED13-PadC)") (class "Default")
      (node (ref "LED13") (pin "C") (pinfunction "C_C") (pintype "passive"))
      (node (ref "R56") (pin "2") (pinfunction "2_2") (pintype "passive"))
    )
    (net (code "60") (name "Net-(LED14-PadC)") (class "Default")
      (node (ref "LED14") (pin "C") (pinfunction "C_C") (pintype "passive"))
      (node (ref "R57") (pin "2") (pinfunction "2_2") (pintype "passive"))
    )
    (net (code "61") (name "Net-(PH1-PadA)") (class "Default")
      (node (ref "PH1") (pin "A") (pinfunction "A_A") (pintype "passive"))
      (node (ref "R40") (pin "1") (pinfunction "1_1") (pintype "passive"))
    )
    (net (code "62") (name "Net-(PH2-PadA)") (class "Default")
      (node (ref "PH2") (pin "A") (pinfunction "A_A") (pintype "passive"))
      (node (ref "R41") (pin "1") (pinfunction "1_1") (pintype "passive"))
    )
    (net (code "63") (name "Net-(PH3-PadA)") (class "Default")
      (node (ref "PH3") (pin "A") (pinfunction "A_A") (pintype "passive"))
      (node (ref "R42") (pin "1") (pinfunction "1_1") (pintype "passive"))
    )
    (net (code "64") (name "Net-(PH4-PadA)") (class "Default")
      (node (ref "PH4") (pin "A") (pinfunction "A_A") (pintype "passive"))
      (node (ref "R43") (pin "1") (pinfunction "1_1") (pintype "passive"))
    )
    (net (code "65") (name "Net-(PH5-PadA)") (class "Default")
      (node (ref "PH5") (pin "A") (pinfunction "A_A") (pintype "passive"))
      (node (ref "R44") (pin "1") (pinfunction "1_1") (pintype "passive"))
    )
    (net (code "66") (name "Net-(PH6-PadA)") (class "Default")
      (node (ref "PH6") (pin "A") (pinfunction "A_A") (pintype "passive"))
      (node (ref "R45") (pin "1") (pinfunction "1_1") (pintype "passive"))
    )
    (net (code "67") (name "Net-(T1-C)") (class "Default")
      (node (ref "R15") (pin "1") (pinfunction "1_1") (pintype "passive"))
      (node (ref "R21") (pin "1") (pinfunction "1_1") (pintype "passive"))
      (node (ref "T1") (pin "3") (pinfunction "C_3") (pintype "passive"))
    )
    (net (code "68") (name "Net-(T2-C)") (class "Default")
      (node (ref "R16") (pin "1") (pinfunction "1_1") (pintype "passive"))
      (node (ref "R22") (pin "1") (pinfunction "1_1") (pintype "passive"))
      (node (ref "T2") (pin "3") (pinfunction "C_3") (pintype "passive"))
    )
    (net (code "69") (name "Net-(T3-C)") (class "Default")
      (node (ref "R17") (pin "1") (pinfunction "1_1") (pintype "passive"))
      (node (ref "R23") (pin "1") (pinfunction "1_1") (pintype "passive"))
      (node (ref "T3") (pin "3") (pinfunction "C_3") (pintype "passive"))
    )
    (net (code "70") (name "Net-(T4-C)") (class "Default")
      (node (ref "R18") (pin "1") (pinfunction "1_1") (pintype "passive"))
      (node (ref "R24") (pin "1") (pinfunction "1_1") (pintype "passive"))
      (node (ref "T4") (pin "3") (pinfunction "C_3") (pintype "passive"))
    )
    (net (code "71") (name "Net-(T5-C)") (class "Default")
      (node (ref "R20") (pin "1") (pinfunction "1_1") (pintype "passive"))
      (node (ref "R26") (pin "1") (pinfunction "1_1") (pintype "passive"))
      (node (ref "T5") (pin "3") (pinfunction "C_3") (pintype "passive"))
    )
    (net (code "72") (name "Net-(T6-C)") (class "Default")
      (node (ref "R19") (pin "1") (pinfunction "1_1") (pintype "passive"))
      (node (ref "R25") (pin "1") (pinfunction "1_1") (pintype "passive"))
      (node (ref "T6") (pin "3") (pinfunction "C_3") (pintype "passive"))
    )
    (net (code "73") (name "Net-(T13-C)") (class "Default")
      (node (ref "R1") (pin "1") (pinfunction "1_1") (pintype "passive"))
      (node (ref "R7") (pin "1") (pinfunction "1_1") (pintype "passive"))
      (node (ref "T13") (pin "3") (pinfunction "C_3") (pintype "passive"))
    )
    (net (code "74") (name "Net-(T14-C)") (class "Default")
      (node (ref "R2") (pin "1") (pinfunction "1_1") (pintype "passive"))
      (node (ref "R8") (pin "1") (pinfunction "1_1") (pintype "passive"))
      (node (ref "T14") (pin "3") (pinfunction "C_3") (pintype "passive"))
    )
    (net (code "75") (name "Net-(T15-C)") (class "Default")
      (node (ref "R3") (pin "1") (pinfunction "1_1") (pintype "passive"))
      (node (ref "R9") (pin "1") (pinfunction "1_1") (pintype "passive"))
      (node (ref "T15") (pin "3") (pinfunction "C_3") (pintype "passive"))
    )
    (net (code "76") (name "Net-(T16-C)") (class "Default")
      (node (ref "R10") (pin "1") (pinfunction "1_1") (pintype "passive"))
      (node (ref "R4") (pin "1") (pinfunction "1_1") (pintype "passive"))
      (node (ref "T16") (pin "3") (pinfunction "C_3") (pintype "passive"))
    )
    (net (code "77") (name "Net-(T17-C)") (class "Default")
      (node (ref "R12") (pin "1") (pinfunction "1_1") (pintype "passive"))
      (node (ref "R6") (pin "1") (pinfunction "1_1") (pintype "passive"))
      (node (ref "T17") (pin "3") (pinfunction "C_3") (pintype "passive"))
    )
    (net (code "78") (name "Net-(T18-C)") (class "Default")
      (node (ref "R11") (pin "1") (pinfunction "1_1") (pintype "passive"))
      (node (ref "R5") (pin "1") (pinfunction "1_1") (pintype "passive"))
      (node (ref "T18") (pin "3") (pinfunction "C_3") (pintype "passive"))
    )
    (net (code "79") (name "Net-(U2-G)") (class "Default")
      (node (ref "R1") (pin "2") (pinfunction "2_2") (pintype "passive"))
      (node (ref "U2") (pin "4") (pinfunction "G_4") (pintype "bidirectional"))
    )
    (net (code "80") (name "Net-(U3-G)") (class "Default")
      (node (ref "R3") (pin "2") (pinfunction "2_2") (pintype "passive"))
      (node (ref "U3") (pin "4") (pinfunction "G_4") (pintype "bidirectional"))
    )
    (net (code "81") (name "Net-(U4-G)") (class "Default")
      (node (ref "R5") (pin "2") (pinfunction "2_2") (pintype "passive"))
      (node (ref "U4") (pin "4") (pinfunction "G_4") (pintype "bidirectional"))
    )
    (net (code "82") (name "Net-(U5-G)") (class "Default")
      (node (ref "R2") (pin "2") (pinfunction "2_2") (pintype "passive"))
      (node (ref "U5") (pin "4") (pinfunction "G_4") (pintype "bidirectional"))
    )
    (net (code "83") (name "Net-(U6-G)") (class "Default")
      (node (ref "R4") (pin "2") (pinfunction "2_2") (pintype "passive"))
      (node (ref "U6") (pin "4") (pinfunction "G_4") (pintype "bidirectional"))
    )
    (net (code "84") (name "Net-(U7-G)") (class "Default")
      (node (ref "R6") (pin "2") (pinfunction "2_2") (pintype "passive"))
      (node (ref "U7") (pin "4") (pinfunction "G_4") (pintype "bidirectional"))
    )
    (net (code "85") (name "Net-(U8-G)") (class "Default")
      (node (ref "R15") (pin "2") (pinfunction "2_2") (pintype "passive"))
      (node (ref "U8") (pin "4") (pinfunction "G_4") (pintype "bidirectional"))
    )
    (net (code "86") (name "Net-(U9-G)") (class "Default")
      (node (ref "R17") (pin "2") (pinfunction "2_2") (pintype "passive"))
      (node (ref "U9") (pin "4") (pinfunction "G_4") (pintype "bidirectional"))
    )
    (net (code "87") (name "Net-(U10-G)") (class "Default")
      (node (ref "R19") (pin "2") (pinfunction "2_2") (pintype "passive"))
      (node (ref "U10") (pin "4") (pinfunction "G_4") (pintype "bidirectional"))
    )
    (net (code "88") (name "Net-(U11-G)") (class "Default")
      (node (ref "R16") (pin "2") (pinfunction "2_2") (pintype "passive"))
      (node (ref "U11") (pin "4") (pinfunction "G_4") (pintype "bidirectional"))
    )
    (net (code "89") (name "Net-(U12-G)") (class "Default")
      (node (ref "R18") (pin "2") (pinfunction "2_2") (pintype "passive"))
      (node (ref "U12") (pin "4") (pinfunction "G_4") (pintype "bidirectional"))
    )
    (net (code "90") (name "Net-(U13-G)") (class "Default")
      (node (ref "R20") (pin "2") (pinfunction "2_2") (pintype "passive"))
      (node (ref "U13") (pin "4") (pinfunction "G_4") (pintype "bidirectional"))
    )
    (net (code "91") (name "SENSE1") (class "Default")
      (node (ref "IC2") (pin "49") (pinfunction "(AD2)PA2_49") (pintype "bidirectional"))
      (node (ref "PH1") (pin "C") (pinfunction "C_C") (pintype "passive"))
      (node (ref "R46") (pin "2") (pinfunction "2_2") (pintype "passive"))
    )
    (net (code "92") (name "SENSE1_ON") (class "Default")
      (node (ref "LED9") (pin "A") (pinfunction "A_A") (pintype "passive"))
    )
    (net (code "93") (name "SENSE2") (class "Default")
      (node (ref "IC2") (pin "48") (pinfunction "(AD3)PA3_48") (pintype "bidirectional"))
      (node (ref "PH2") (pin "C") (pinfunction "C_C") (pintype "passive"))
      (node (ref "R47") (pin "2") (pinfunction "2_2") (pintype "passive"))
    )
    (net (code "94") (name "SENSE2_ON") (class "Default")
      (node (ref "LED10") (pin "A") (pinfunction "A_A") (pintype "passive"))
    )
    (net (code "95") (name "SENSE3") (class "Default")
      (node (ref "IC2") (pin "47") (pinfunction "(AD4)PA4_47") (pintype "bidirectional"))
      (node (ref "PH3") (pin "C") (pinfunction "C_C") (pintype "passive"))
      (node (ref "R48") (pin "2") (pinfunction "2_2") (pintype "passive"))
    )
    (net (code "96") (name "SENSE3_ON") (class "Default")
      (node (ref "LED11") (pin "A") (pinfunction "A_A") (pintype "passive"))
    )
    (net (code "97") (name "SENSE4") (class "Default")
      (node (ref "IC2") (pin "46") (pinfunction "(AD5)PA5_46") (pintype "bidirectional"))
      (node (ref "PH4") (pin "C") (pinfunction "C_C") (pintype "passive"))
      (node (ref "R49") (pin "2") (pinfunction "2_2") (pintype "passive"))
    )
    (net (code "98") (name "SENSE4_ON") (class "Default")
      (node (ref "LED12") (pin "A") (pinfunction "A_A") (pintype "passive"))
    )
    (net (code "99") (name "SENSE5") (class "Default")
      (node (ref "IC2") (pin "45") (pinfunction "(AD6)PA6_45") (pintype "bidirectional"))
      (node (ref "PH5") (pin "C") (pinfunction "C_C") (pintype "passive"))
      (node (ref "R50") (pin "2") (pinfunction "2_2") (pintype "passive"))
    )
    (net (code "100") (name "SENSE5_ON") (class "Default")
      (node (ref "LED13") (pin "A") (pinfunction "A_A") (pintype "passive"))
    )
    (net (code "101") (name "SENSE6") (class "Default")
      (node (ref "IC2") (pin "44") (pinfunction "(AD7)PA7_44") (pintype "bidirectional"))
      (node (ref "PH6") (pin "C") (pinfunction "C_C") (pintype "passive"))
      (node (ref "R51") (pin "2") (pinfunction "2_2") (pintype "passive"))
    )
    (net (code "102") (name "SENSE6_ON") (class "Default")
      (node (ref "LED14") (pin "A") (pinfunction "A_A") (pintype "passive"))
    )
    (net (code "103") (name "V+") (class "Default")
      (node (ref "C1") (pin "+") (pinfunction "+_+") (pintype "passive"))
      (node (ref "C21") (pin "1") (pinfunction "1_1") (pintype "passive"))
      (node (ref "C22") (pin "1") (pinfunction "1_1") (pintype "passive"))
      (node (ref "C23") (pin "1") (pinfunction "1_1") (pintype "passive"))
      (node (ref "C32") (pin "1") (pinfunction "1_1") (pintype "passive"))
      (node (ref "C33") (pin "1") (pinfunction "1_1") (pintype "passive"))
      (node (ref "C34") (pin "1") (pinfunction "1_1") (pintype "passive"))
      (node (ref "IC3") (pin "1") (pinfunction "VIN_1") (pintype "input"))
      (node (ref "IC5") (pin "1") (pinfunction "VIN_1") (pintype "input"))
      (node (ref "R10") (pin "2") (pinfunction "2_2") (pintype "passive"))
      (node (ref "R11") (pin "2") (pinfunction "2_2") (pintype "passive"))
      (node (ref "R12") (pin "2") (pinfunction "2_2") (pintype "passive"))
      (node (ref "R21") (pin "2") (pinfunction "2_2") (pintype "passive"))
      (node (ref "R22") (pin "2") (pinfunction "2_2") (pintype "passive"))
      (node (ref "R23") (pin "2") (pinfunction "2_2") (pintype "passive"))
      (node (ref "R24") (pin "2") (pinfunction "2_2") (pintype "passive"))
      (node (ref "R25") (pin "2") (pinfunction "2_2") (pintype "passive"))
      (node (ref "R26") (pin "2") (pinfunction "2_2") (pintype "passive"))
      (node (ref "R7") (pin "2") (pinfunction "2_2") (pintype "passive"))
      (node (ref "R8") (pin "2") (pinfunction "2_2") (pintype "passive"))
      (node (ref "R9") (pin "2") (pinfunction "2_2") (pintype "passive"))
      (node (ref "U10") (pin "1") (pinfunction "S_1") (pintype "bidirectional"))
      (node (ref "U10") (pin "2") (pinfunction "S_2") (pintype "bidirectional"))
      (node (ref "U10") (pin "3") (pinfunction "S_3") (pintype "bidirectional"))
      (node (ref "U2") (pin "1") (pinfunction "S_1") (pintype "bidirectional"))
      (node (ref "U2") (pin "2") (pinfunction "S_2") (pintype "bidirectional"))
      (node (ref "U2") (pin "3") (pinfunction "S_3") (pintype "bidirectional"))
      (node (ref "U3") (pin "1") (pinfunction "S_1") (pintype "bidirectional"))
      (node (ref "U3") (pin "2") (pinfunction "S_2") (pintype "bidirectional"))
      (node (ref "U3") (pin "3") (pinfunction "S_3") (pintype "bidirectional"))
      (node (ref "U4") (pin "1") (pinfunction "S_1") (pintype "bidirectional"))
      (node (ref "U4") (pin "2") (pinfunction "S_2") (pintype "bidirectional"))
      (node (ref "U4") (pin "3") (pinfunction "S_3") (pintype "bidirectional"))
      (node (ref "U8") (pin "1") (pinfunction "S_1") (pintype "bidirectional"))
      (node (ref "U8") (pin "2") (pinfunction "S_2") (pintype "bidirectional"))
      (node (ref "U8") (pin "3") (pinfunction "S_3") (pintype "bidirectional"))
      (node (ref "U9") (pin "1") (pinfunction "S_1") (pintype "bidirectional"))
      (node (ref "U9") (pin "2") (pinfunction "S_2") (pintype "bidirectional"))
      (node (ref "U9") (pin "3") (pinfunction "S_3") (pintype "bidirectional"))
      (node (ref "VCC") (pin "1") (pinfunction "1_1") (pintype "bidirectional"))
    )
    (net (code "104") (name "unconnected-(IC1-ADC6-Pad19)") (class "Default")
      (node (ref "IC1") (pin "19") (pinfunction "ADC6_19") (pintype "bidirectional"))
    )
    (net (code "105") (name "unconnected-(IC1-ADC7-Pad22)") (class "Default")
      (node (ref "IC1") (pin "22") (pinfunction "ADC7_22") (pintype "bidirectional"))
    )
    (net (code "106") (name "unconnected-(IC1-AREF-Pad20)") (class "Default")
      (node (ref "IC1") (pin "20") (pinfunction "AREF_20") (pintype "passive"))
    )
    (net (code "107") (name "unconnected-(IC1-PC0(ADC0)-Pad23)") (class "Default")
      (node (ref "IC1") (pin "23") (pinfunction "PC0(ADC0)_23") (pintype "bidirectional"))
    )
    (net (code "108") (name "unconnected-(IC1-PC1(ADC1)-Pad24)") (class "Default")
      (node (ref "IC1") (pin "24") (pinfunction "PC1(ADC1)_24") (pintype "bidirectional"))
    )
    (net (code "109") (name "unconnected-(IC1-PC2(ADC2)-Pad25)") (class "Default")
      (node (ref "IC1") (pin "25") (pinfunction "PC2(ADC2)_25") (pintype "bidirectional"))
    )
    (net (code "110") (name "unconnected-(IC1-PC3(ADC3)-Pad26)") (class "Default")
      (node (ref "IC1") (pin "26") (pinfunction "PC3(ADC3)_26") (pintype "bidirectional"))
    )
    (net (code "111") (name "unconnected-(IC1-PC4(ADC4{slash}SDA)-Pad27)") (class "Default")
      (node (ref "IC1") (pin "27") (pinfunction "PC4(ADC4/SDA)_27") (pintype "bidirectional"))
    )
    (net (code "112") (name "unconnected-(IC1-PC5(ADC5{slash}SCL)-Pad28)") (class "Default")
      (node (ref "IC1") (pin "28") (pinfunction "PC5(ADC5/SCL)_28") (pintype "bidirectional"))
    )
    (net (code "113") (name "unconnected-(IC1-PD0(RXD)-Pad30)") (class "Default")
      (node (ref "IC1") (pin "30") (pinfunction "PD0(RXD)_30") (pintype "bidirectional"))
    )
    (net (code "114") (name "unconnected-(IC1-PD3(INT1)-Pad1)") (class "Default")
      (node (ref "IC1") (pin "1") (pinfunction "PD3(INT1)_1") (pintype "bidirectional"))
    )
    (net (code "115") (name "unconnected-(IC1-PD4(XCK{slash}T0)-Pad2)") (class "Default")
      (node (ref "IC1") (pin "2") (pinfunction "PD4(XCK/T0)_2") (pintype "bidirectional"))
    )
    (net (code "116") (name "unconnected-(IC1-PD5(T1)-Pad9)") (class "Default")
      (node (ref "IC1") (pin "9") (pinfunction "PD5(T1)_9") (pintype "bidirectional"))
    )
    (net (code "117") (name "unconnected-(IC1-PD6(AIN0)-Pad10)") (class "Default")
      (node (ref "IC1") (pin "10") (pinfunction "PD6(AIN0)_10") (pintype "bidirectional"))
    )
    (net (code "118") (name "unconnected-(IC1-PD7(AIN1)-Pad11)") (class "Default")
      (node (ref "IC1") (pin "11") (pinfunction "PD7(AIN1)_11") (pintype "bidirectional"))
    )
    (net (code "119") (name "unconnected-(IC2-(A8)PC0-Pad35)") (class "Default")
      (node (ref "IC2") (pin "35") (pinfunction "(A8)PC0_35") (pintype "output"))
    )
    (net (code "120") (name "unconnected-(IC2-(A9)PC1-Pad36)") (class "Default")
      (node (ref "IC2") (pin "36") (pinfunction "(A9)PC1_36") (pintype "output"))
    )
    (net (code "121") (name "unconnected-(IC2-(A10)PC2-Pad37)") (class "Default")
      (node (ref "IC2") (pin "37") (pinfunction "(A10)PC2_37") (pintype "output"))
    )
    (net (code "122") (name "unconnected-(IC2-(A11)PC3-Pad38)") (class "Default")
      (node (ref "IC2") (pin "38") (pinfunction "(A11)PC3_38") (pintype "output"))
    )
    (net (code "123") (name "unconnected-(IC2-(A12)PC4-Pad39)") (class "Default")
      (node (ref "IC2") (pin "39") (pinfunction "(A12)PC4_39") (pintype "output"))
    )
    (net (code "124") (name "unconnected-(IC2-(A13)PC5-Pad40)") (class "Default")
      (node (ref "IC2") (pin "40") (pinfunction "(A13)PC5_40") (pintype "output"))
    )
    (net (code "125") (name "unconnected-(IC2-(A14)PC6-Pad41)") (class "Default")
      (node (ref "IC2") (pin "41") (pinfunction "(A14)PC6_41") (pintype "output"))
    )
    (net (code "126") (name "unconnected-(IC2-(A15)PC7-Pad42)") (class "Default")
      (node (ref "IC2") (pin "42") (pinfunction "(A15)PC7_42") (pintype "output"))
    )
    (net (code "127") (name "unconnected-(IC2-(AD0)PA0-Pad51)") (class "Default")
      (node (ref "IC2") (pin "51") (pinfunction "(AD0)PA0_51") (pintype "bidirectional"))
    )
    (net (code "128") (name "unconnected-(IC2-(AD1)PA1-Pad50)") (class "Default")
      (node (ref "IC2") (pin "50") (pinfunction "(AD1)PA1_50") (pintype "bidirectional"))
    )
    (net (code "129") (name "unconnected-(IC2-(IC3{slash}INT7)PE7-Pad9)") (class "Default")
      (node (ref "IC2") (pin "9") (pinfunction "(IC3/INT7)PE7_9") (pintype "bidirectional"))
    )
    (net (code "130") (name "unconnected-(IC2-(MISO)PB3-Pad13)") (class "Default")
      (node (ref "IC2") (pin "13") (pinfunction "(MISO)PB3_13") (pintype "bidirectional"))
    )
    (net (code "131") (name "unconnected-(IC2-(MOSI)PB2-Pad12)") (class "Default")
      (node (ref "IC2") (pin "12") (pinfunction "(MOSI)PB2_12") (pintype "bidirectional"))
    )
    (net (code "132") (name "unconnected-(IC2-(OC0)PB4-Pad14)") (class "Default")
      (node (ref "IC2") (pin "14") (pinfunction "(OC0)PB4_14") (pintype "bidirectional"))
    )
    (net (code "133") (name "unconnected-(IC2-(OC1A)PB5-Pad15)") (class "Default")
      (node (ref "IC2") (pin "15") (pinfunction "(OC1A)PB5_15") (pintype "bidirectional"))
    )
    (net (code "134") (name "unconnected-(IC2-(OC1B)PB6-Pad16)") (class "Default")
      (node (ref "IC2") (pin "16") (pinfunction "(OC1B)PB6_16") (pintype "bidirectional"))
    )
    (net (code "135") (name "unconnected-(IC2-(OC2{slash}OC1C)PB7-Pad17)") (class "Default")
      (node (ref "IC2") (pin "17") (pinfunction "(OC2/OC1C)PB7_17") (pintype "bidirectional"))
    )
    (net (code "136") (name "unconnected-(IC2-(OC3A{slash}AIN1)PE3-Pad5)") (class "Default")
      (node (ref "IC2") (pin "5") (pinfunction "(OC3A/AIN1)PE3_5") (pintype "bidirectional"))
    )
    (net (code "137") (name "unconnected-(IC2-(OC3B{slash}INT4)PE4-Pad6)") (class "Default")
      (node (ref "IC2") (pin "6") (pinfunction "(OC3B/INT4)PE4_6") (pintype "bidirectional"))
    )
    (net (code "138") (name "unconnected-(IC2-(OC3C{slash}INT5)PE5-Pad7)") (class "Default")
      (node (ref "IC2") (pin "7") (pinfunction "(OC3C/INT5)PE5_7") (pintype "bidirectional"))
    )
    (net (code "139") (name "unconnected-(IC2-(RXD1{slash}INT2)PD2-Pad27)") (class "Default")
      (node (ref "IC2") (pin "27") (pinfunction "(RXD1/INT2)PD2_27") (pintype "bidirectional"))
    )
    (net (code "140") (name "unconnected-(IC2-(RXD{slash}PDI)PE0-Pad2)") (class "Default")
      (node (ref "IC2") (pin "2") (pinfunction "(RXD/PDI)PE0_2") (pintype "bidirectional"))
    )
    (net (code "141") (name "unconnected-(IC2-(SCK)PB1-Pad11)") (class "Default")
      (node (ref "IC2") (pin "11") (pinfunction "(SCK)PB1_11") (pintype "bidirectional"))
    )
    (net (code "142") (name "unconnected-(IC2-(SCL{slash}INT0)PD0-Pad25)") (class "Default")
      (node (ref "IC2") (pin "25") (pinfunction "(SCL/INT0)PD0_25") (pintype "bidirectional"))
    )
    (net (code "143") (name "unconnected-(IC2-(SDA{slash}INT1)PD1-Pad26)") (class "Default")
      (node (ref "IC2") (pin "26") (pinfunction "(SDA/INT1)PD1_26") (pintype "bidirectional"))
    )
    (net (code "144") (name "unconnected-(IC2-(SS)PB0-Pad10)") (class "Default")
      (node (ref "IC2") (pin "10") (pinfunction "(SS)PB0_10") (pintype "bidirectional"))
    )
    (net (code "145") (name "unconnected-(IC2-(T2)PD7-Pad32)") (class "Default")
      (node (ref "IC2") (pin "32") (pinfunction "(T2)PD7_32") (pintype "bidirectional"))
    )
    (net (code "146") (name "unconnected-(IC2-(T3{slash}INT6)PE6-Pad8)") (class "Default")
      (node (ref "IC2") (pin "8") (pinfunction "(T3/INT6)PE6_8") (pintype "bidirectional"))
    )
    (net (code "147") (name "unconnected-(IC2-(TXD{slash}PDO)PE1-Pad3)") (class "Default")
      (node (ref "IC2") (pin "3") (pinfunction "(TXD/PDO)PE1_3") (pintype "bidirectional"))
    )
    (net (code "148") (name "unconnected-(IC2-(XCK0{slash}AIN0)PE2-Pad4)") (class "Default")
      (node (ref "IC2") (pin "4") (pinfunction "(XCK0/AIN0)PE2_4") (pintype "bidirectional"))
    )
    (net (code "149") (name "unconnected-(IC2-AREF-Pad62)") (class "Default")
      (node (ref "IC2") (pin "62") (pinfunction "AREF_62") (pintype "passive"))
    )
    (net (code "150") (name "unconnected-(IC2-PEN-Pad1)") (class "Default")
      (node (ref "IC2") (pin "1") (pinfunction "PEN_1") (pintype "input"))
    )
    (net (code "151") (name "unconnected-(IC2-PF0(ADC0)-Pad61)") (class "Default")
      (node (ref "IC2") (pin "61") (pinfunction "PF0(ADC0)_61") (pintype "input"))
    )
    (net (code "152") (name "unconnected-(IC2-PF1(ADC1)-Pad60)") (class "Default")
      (node (ref "IC2") (pin "60") (pinfunction "PF1(ADC1)_60") (pintype "input"))
    )
    (net (code "153") (name "unconnected-(IC2-PF2(ADC2)-Pad59)") (class "Default")
      (node (ref "IC2") (pin "59") (pinfunction "PF2(ADC2)_59") (pintype "input"))
    )
    (net (code "154") (name "unconnected-(IC2-PF3(ADC3)-Pad58)") (class "Default")
      (node (ref "IC2") (pin "58") (pinfunction "PF3(ADC3)_58") (pintype "input"))
    )
    (net (code "155") (name "unconnected-(IC2-PF4(ADC4{slash}TCK)-Pad57)") (class "Default")
      (node (ref "IC2") (pin "57") (pinfunction "PF4(ADC4/TCK)_57") (pintype "input"))
    )
    (net (code "156") (name "unconnected-(IC2-PF5(ADC5{slash}TMS)-Pad56)") (class "Default")
      (node (ref "IC2") (pin "56") (pinfunction "PF5(ADC5/TMS)_56") (pintype "input"))
    )
    (net (code "157") (name "unconnected-(IC2-PF6(ADC6{slash}TDO)-Pad55)") (class "Default")
      (node (ref "IC2") (pin "55") (pinfunction "PF6(ADC6/TDO)_55") (pintype "input"))
    )
    (net (code "158") (name "unconnected-(IC2-PF7(ADC7{slash}TDI)-Pad54)") (class "Default")
      (node (ref "IC2") (pin "54") (pinfunction "PF7(ADC7/TDI)_54") (pintype "input"))
    )
    (net (code "159") (name "unconnected-(IC2-PG0(WR)-Pad33)") (class "Default")
      (node (ref "IC2") (pin "33") (pinfunction "PG0(WR)_33") (pintype "bidirectional"))
    )
    (net (code "160") (name "unconnected-(IC2-PG1(RD)-Pad34)") (class "Default")
      (node (ref "IC2") (pin "34") (pinfunction "PG1(RD)_34") (pintype "bidirectional"))
    )
    (net (code "161") (name "unconnected-(IC2-PG2(ALE)-Pad43)") (class "Default")
      (node (ref "IC2") (pin "43") (pinfunction "PG2(ALE)_43") (pintype "bidirectional"))
    )
    (net (code "162") (name "unconnected-(IC2-PG3(TOSC2)-Pad18)") (class "Default")
      (node (ref "IC2") (pin "18") (pinfunction "PG3(TOSC2)_18") (pintype "bidirectional"))
    )
    (net (code "163") (name "unconnected-(IC2-PG4(TOSC1)-Pad19)") (class "Default")
      (node (ref "IC2") (pin "19") (pinfunction "PG4(TOSC1)_19") (pintype "bidirectional"))
    )
    (net (code "164") (name "unconnected-(IC4-ADC6-Pad19)") (class "Default")
      (node (ref "IC4") (pin "19") (pinfunction "ADC6_19") (pintype "bidirectional"))
    )
    (net (code "165") (name "unconnected-(IC4-ADC7-Pad22)") (class "Default")
      (node (ref "IC4") (pin "22") (pinfunction "ADC7_22") (pintype "bidirectional"))
    )
    (net (code "166") (name "unconnected-(IC4-AREF-Pad20)") (class "Default")
      (node (ref "IC4") (pin "20") (pinfunction "AREF_20") (pintype "passive"))
    )
    (net (code "167") (name "unconnected-(IC4-PC0(ADC0)-Pad23)") (class "Default")
      (node (ref "IC4") (pin "23") (pinfunction "PC0(ADC0)_23") (pintype "bidirectional"))
    )
    (net (code "168") (name "unconnected-(IC4-PC1(ADC1)-Pad24)") (class "Default")
      (node (ref "IC4") (pin "24") (pinfunction "PC1(ADC1)_24") (pintype "bidirectional"))
    )
    (net (code "169") (name "unconnected-(IC4-PC2(ADC2)-Pad25)") (class "Default")
      (node (ref "IC4") (pin "25") (pinfunction "PC2(ADC2)_25") (pintype "bidirectional"))
    )
    (net (code "170") (name "unconnected-(IC4-PC3(ADC3)-Pad26)") (class "Default")
      (node (ref "IC4") (pin "26") (pinfunction "PC3(ADC3)_26") (pintype "bidirectional"))
    )
    (net (code "171") (name "unconnected-(IC4-PC4(ADC4{slash}SDA)-Pad27)") (class "Default")
      (node (ref "IC4") (pin "27") (pinfunction "PC4(ADC4/SDA)_27") (pintype "bidirectional"))
    )
    (net (code "172") (name "unconnected-(IC4-PC5(ADC5{slash}SCL)-Pad28)") (class "Default")
      (node (ref "IC4") (pin "28") (pinfunction "PC5(ADC5/SCL)_28") (pintype "bidirectional"))
    )
    (net (code "173") (name "unconnected-(IC4-PD0(RXD)-Pad30)") (class "Default")
      (node (ref "IC4") (pin "30") (pinfunction "PD0(RXD)_30") (pintype "bidirectional"))
    )
    (net (code "174") (name "unconnected-(IC4-PD3(INT1)-Pad1)") (class "Default")
      (node (ref "IC4") (pin "1") (pinfunction "PD3(INT1)_1") (pintype "bidirectional"))
    )
    (net (code "175") (name "unconnected-(IC4-PD4(XCK{slash}T0)-Pad2)") (class "Default")
      (node (ref "IC4") (pin "2") (pinfunction "PD4(XCK/T0)_2") (pintype "bidirectional"))
    )
    (net (code "176") (name "unconnected-(IC4-PD5(T1)-Pad9)") (class "Default")
      (node (ref "IC4") (pin "9") (pinfunction "PD5(T1)_9") (pintype "bidirectional"))
    )
    (net (code "177") (name "unconnected-(IC4-PD6(AIN0)-Pad10)") (class "Default")
      (node (ref "IC4") (pin "10") (pinfunction "PD6(AIN0)_10") (pintype "bidirectional"))
    )
    (net (code "178") (name "unconnected-(IC4-PD7(AIN1)-Pad11)") (class "Default")
      (node (ref "IC4") (pin "11") (pinfunction "PD7(AIN1)_11") (pintype "bidirectional"))
    )
  )
)
